# Sheet1.net
KiCad netlist of a schematic drawn in Altium Designer
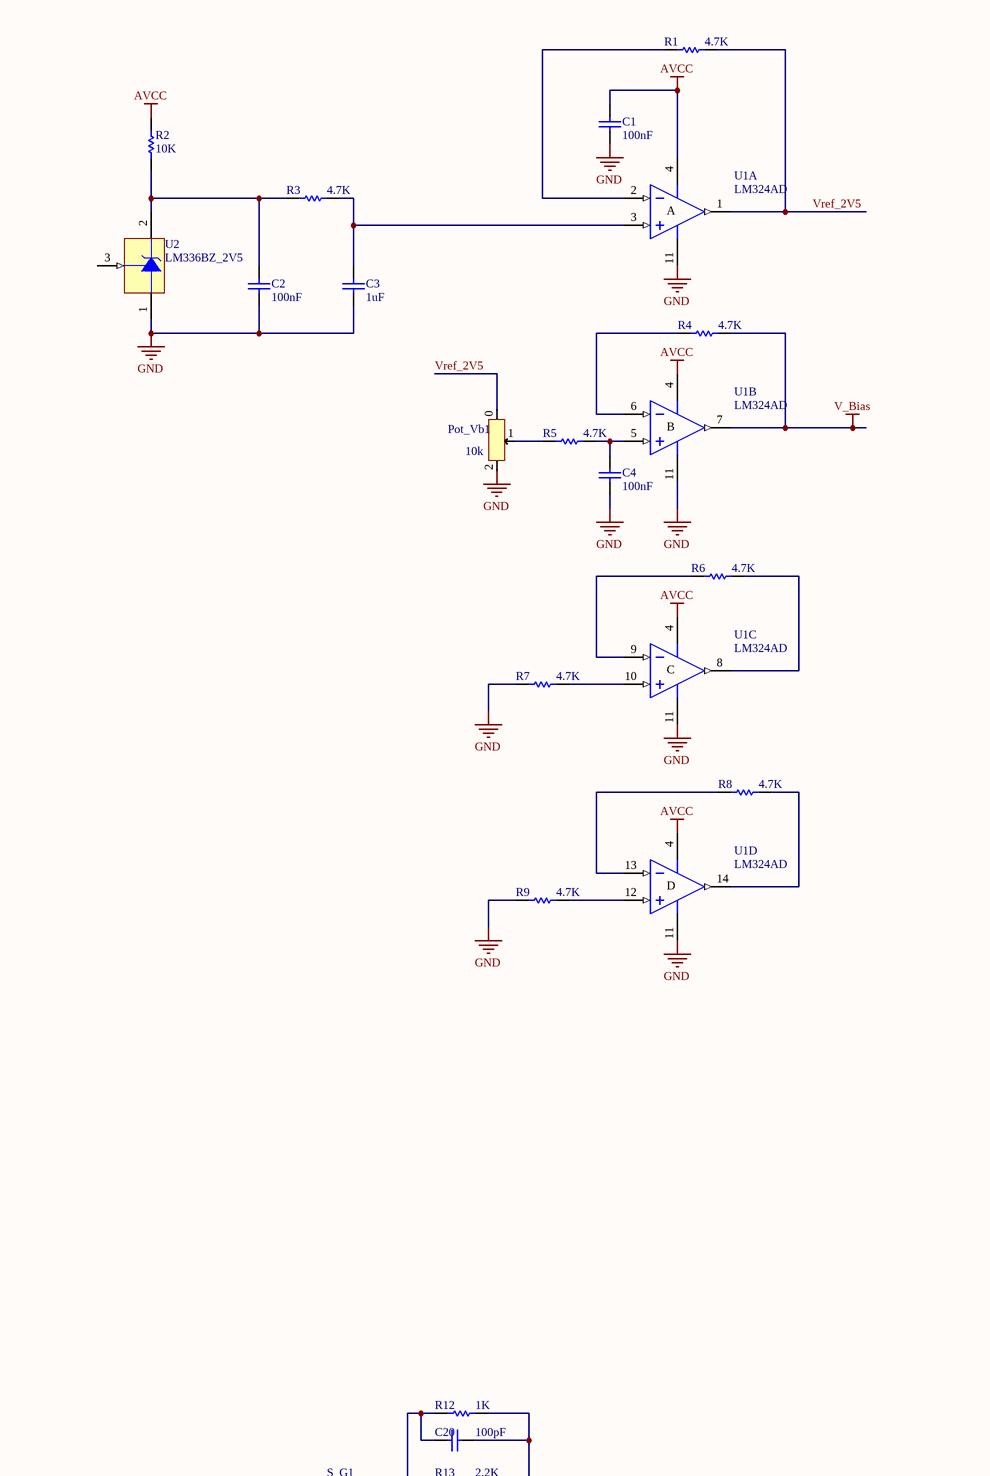
[diagram p0: Sheet1.SchDoc, top left]
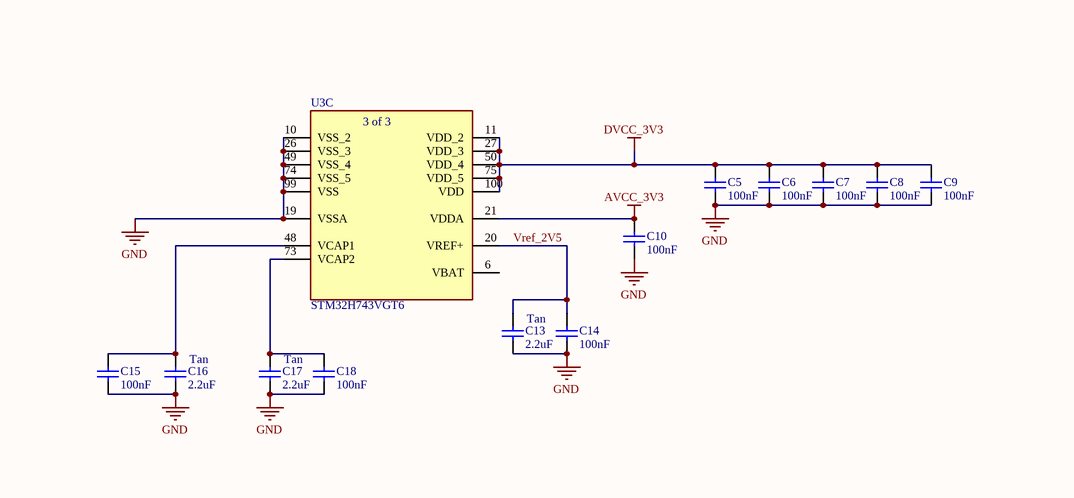
[diagram p1: Sheet1.SchDoc, top middle]
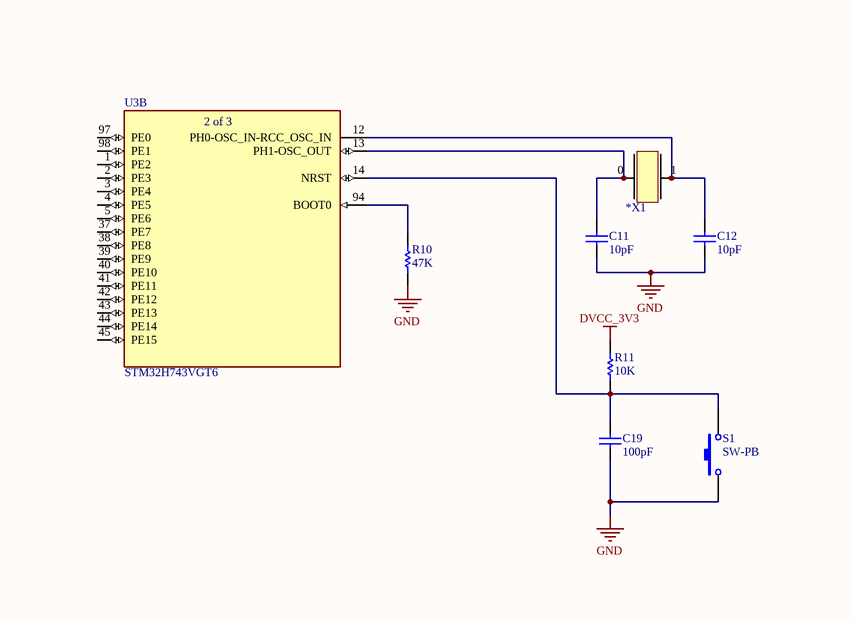
[diagram p2: Sheet1.SchDoc, top right]
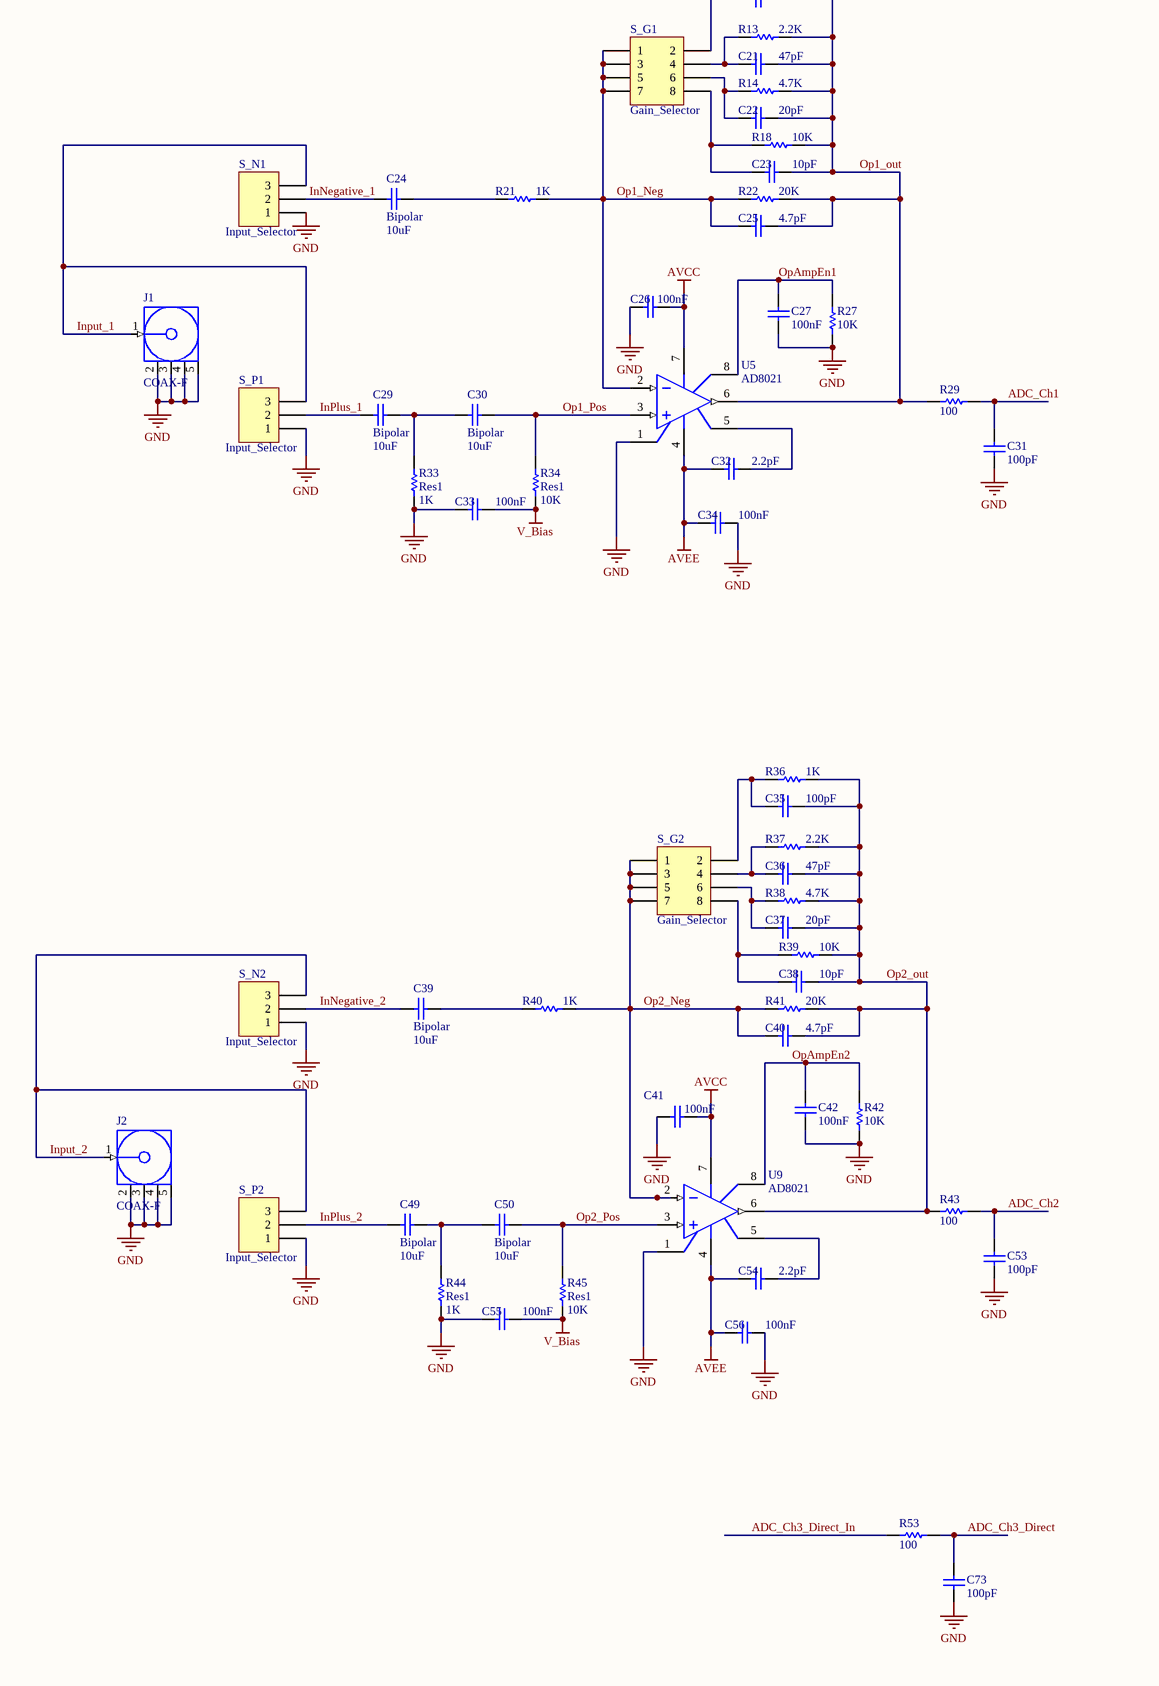
[diagram p3: Sheet1.SchDoc, bottom left]
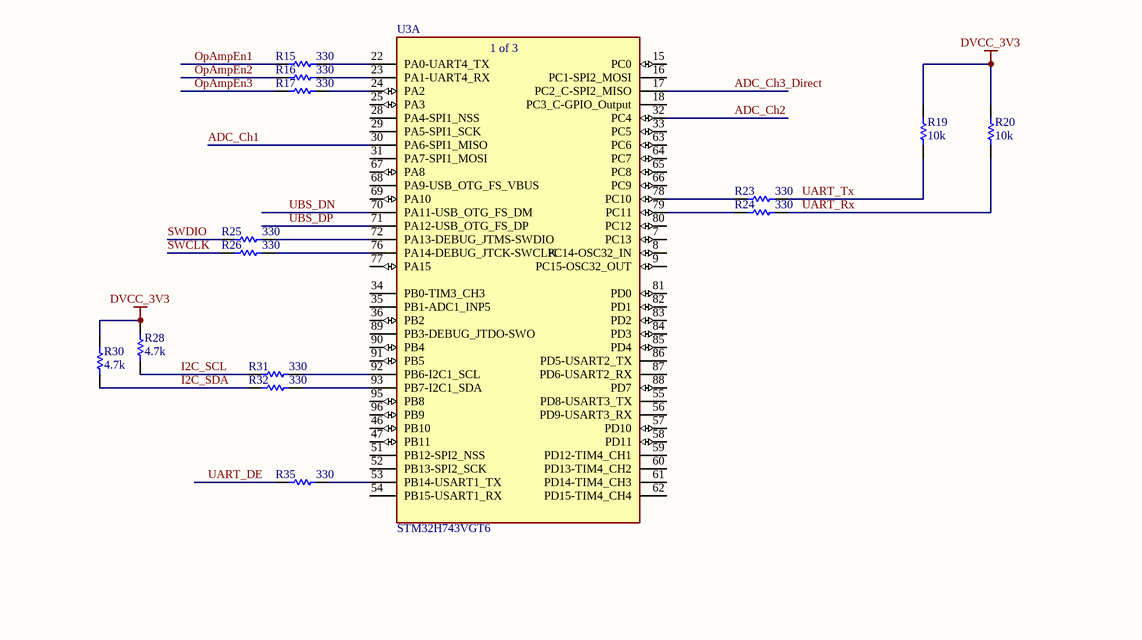
[diagram p4: Sheet1.SchDoc, bottom middle]
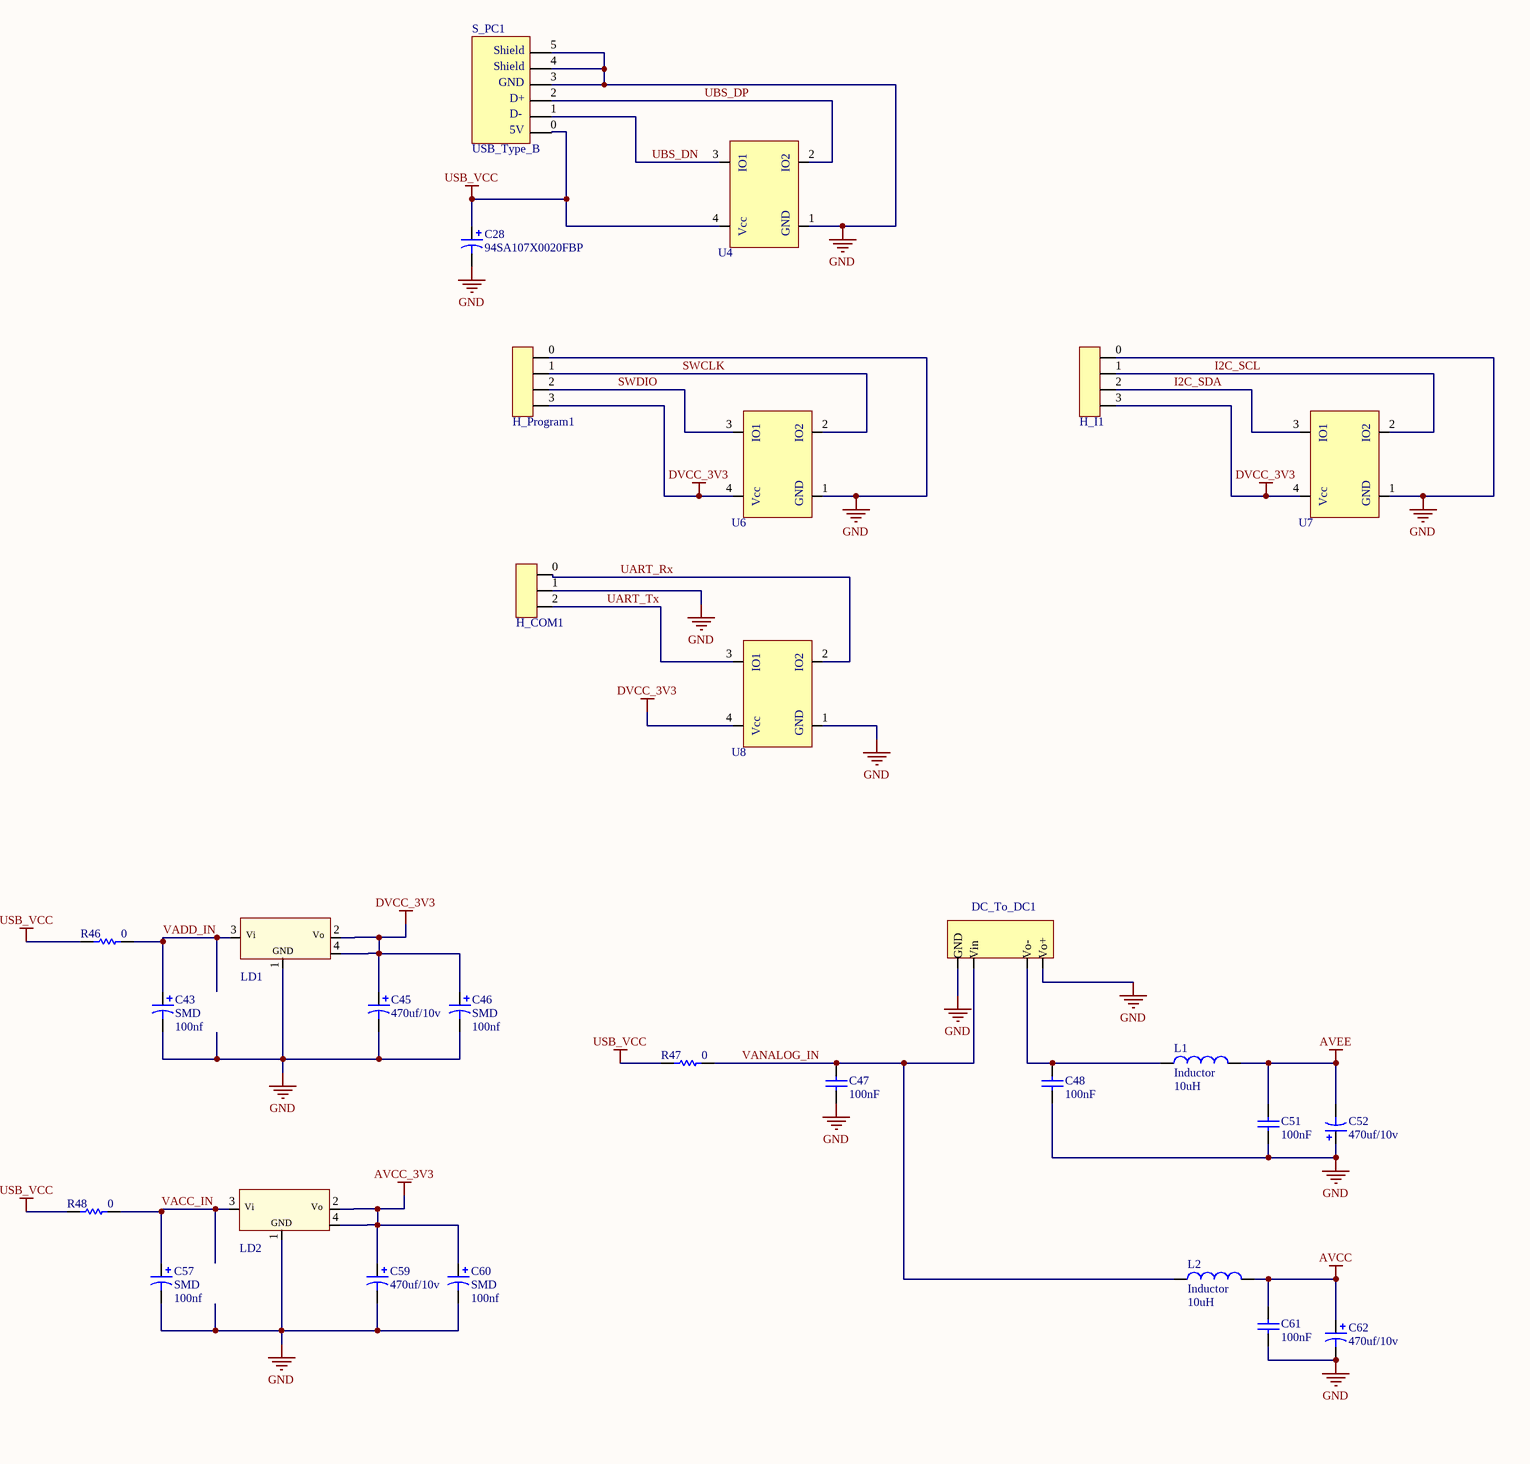
[diagram p5: Sheet1.SchDoc, bottom right]

(export (version "E")
  (design (tool "Eeschema 10.0.6"))
  (components
    (comp (ref "*X1")
      (value "XTAl_Large")
      (footprint "XTAL_Large")
      (libsource (lib "Integrated_Library") (part "XTAl_Large"))
    )
    (comp (ref "C1")
      (value "100nF")
      (footprint "C0805")
      (description "Capacitor")
      (fields (field (name "Comment") "Bipolar") (field (name "PUBLISHER") "Altium Limited"))
      (libsource (lib "Miscellaneous Devices") (part "Cap"))
    )
    (comp (ref "C2")
      (value "100nF")
      (footprint "C0805")
      (description "Capacitor")
      (fields (field (name "Comment") "Bipolar") (field (name "PUBLISHER") "Altium Limited"))
      (libsource (lib "Miscellaneous Devices") (part "Cap"))
    )
    (comp (ref "C3")
      (value "1uF")
      (footprint "C0805")
      (description "Capacitor")
      (fields (field (name "Comment") "Bipolar") (field (name "PUBLISHER") "Altium Limited"))
      (libsource (lib "Miscellaneous Devices") (part "Cap"))
    )
    (comp (ref "C4")
      (value "100nF")
      (footprint "C0805")
      (description "Capacitor")
      (fields (field (name "Comment") "Bipolar") (field (name "PUBLISHER") "Altium Limited"))
      (libsource (lib "Miscellaneous Devices") (part "Cap"))
    )
    (comp (ref "C5")
      (value "100nF")
      (footprint "C0805")
      (description "Capacitor")
      (fields (field (name "Comment") "Bipolar") (field (name "PUBLISHER") "Altium Limited"))
      (libsource (lib "Miscellaneous Devices") (part "Cap"))
    )
    (comp (ref "C6")
      (value "100nF")
      (footprint "C0805")
      (description "Capacitor")
      (fields (field (name "Comment") "Bipolar") (field (name "PUBLISHER") "Altium Limited"))
      (libsource (lib "Miscellaneous Devices") (part "Cap"))
    )
    (comp (ref "C7")
      (value "100nF")
      (footprint "C0805")
      (description "Capacitor")
      (fields (field (name "Comment") "Bipolar") (field (name "PUBLISHER") "Altium Limited"))
      (libsource (lib "Miscellaneous Devices") (part "Cap"))
    )
    (comp (ref "C8")
      (value "100nF")
      (footprint "C0805")
      (description "Capacitor")
      (fields (field (name "Comment") "Bipolar") (field (name "PUBLISHER") "Altium Limited"))
      (libsource (lib "Miscellaneous Devices") (part "Cap"))
    )
    (comp (ref "C9")
      (value "100nF")
      (footprint "C0805")
      (description "Capacitor")
      (fields (field (name "Comment") "Bipolar") (field (name "PUBLISHER") "Altium Limited"))
      (libsource (lib "Miscellaneous Devices") (part "Cap"))
    )
    (comp (ref "C10")
      (value "100nF")
      (footprint "C0805")
      (description "Capacitor")
      (fields (field (name "Comment") "Bipolar") (field (name "PUBLISHER") "Altium Limited"))
      (libsource (lib "Miscellaneous Devices") (part "Cap"))
    )
    (comp (ref "C11")
      (value "10pF")
      (footprint "C0805")
      (description "Capacitor")
      (fields (field (name "Comment") "Bipolar") (field (name "PUBLISHER") "Altium Limited"))
      (libsource (lib "Miscellaneous Devices") (part "Cap"))
    )
    (comp (ref "C12")
      (value "10pF")
      (footprint "C0805")
      (description "Capacitor")
      (fields (field (name "Comment") "Bipolar") (field (name "PUBLISHER") "Altium Limited"))
      (libsource (lib "Miscellaneous Devices") (part "Cap"))
    )
    (comp (ref "C13")
      (value "Tan")
      (footprint "C1210")
      (description "Capacitor")
      (fields (field (name "ALTIUM_VALUE") "2.2uF") (field (name "PUBLISHER") "Altium Limited"))
      (libsource (lib "Miscellaneous Devices") (part "Cap"))
    )
    (comp (ref "C14")
      (value "100nF")
      (footprint "C0805")
      (description "Capacitor")
      (fields (field (name "Comment") "Bipolar") (field (name "PUBLISHER") "Altium Limited"))
      (libsource (lib "Miscellaneous Devices") (part "Cap"))
    )
    (comp (ref "C15")
      (value "100nF")
      (footprint "C0805")
      (description "Capacitor")
      (fields (field (name "Comment") "Bipolar") (field (name "PUBLISHER") "Altium Limited"))
      (libsource (lib "Miscellaneous Devices") (part "Cap"))
    )
    (comp (ref "C16")
      (value "Tan")
      (footprint "C1210")
      (description "Capacitor")
      (fields (field (name "ALTIUM_VALUE") "2.2uF") (field (name "PUBLISHER") "Altium Limited"))
      (libsource (lib "Miscellaneous Devices") (part "Cap"))
    )
    (comp (ref "C17")
      (value "Tan")
      (footprint "C1210")
      (description "Capacitor")
      (fields (field (name "ALTIUM_VALUE") "2.2uF") (field (name "PUBLISHER") "Altium Limited"))
      (libsource (lib "Miscellaneous Devices") (part "Cap"))
    )
    (comp (ref "C18")
      (value "100nF")
      (footprint "C0805")
      (description "Capacitor")
      (fields (field (name "Comment") "Bipolar") (field (name "PUBLISHER") "Altium Limited"))
      (libsource (lib "Miscellaneous Devices") (part "Cap"))
    )
    (comp (ref "C19")
      (value "100pF")
      (footprint "C0805")
      (description "Capacitor")
      (fields (field (name "Comment") "Bipolar") (field (name "PUBLISHER") "Altium Limited"))
      (libsource (lib "Miscellaneous Devices") (part "Cap"))
    )
    (comp (ref "C20")
      (value "100pF")
      (footprint "C0805")
      (description "Capacitor")
      (fields (field (name "Comment") "Bipolar") (field (name "PUBLISHER") "Altium Limited"))
      (libsource (lib "Miscellaneous Devices") (part "Cap"))
    )
    (comp (ref "C21")
      (value "47pF")
      (footprint "C0805")
      (description "Capacitor")
      (fields (field (name "Comment") "Bipolar") (field (name "PUBLISHER") "Altium Limited"))
      (libsource (lib "Miscellaneous Devices") (part "Cap"))
    )
    (comp (ref "C22")
      (value "20pF")
      (footprint "C0805")
      (description "Capacitor")
      (fields (field (name "Comment") "Bipolar") (field (name "PUBLISHER") "Altium Limited"))
      (libsource (lib "Miscellaneous Devices") (part "Cap"))
    )
    (comp (ref "C23")
      (value "10pF")
      (footprint "C0805")
      (description "Capacitor")
      (fields (field (name "Comment") "Bipolar") (field (name "PUBLISHER") "Altium Limited"))
      (libsource (lib "Miscellaneous Devices") (part "Cap"))
    )
    (comp (ref "C24")
      (value "Bipolar")
      (footprint "HA-N3")
      (description "Capacitor")
      (fields (field (name "ALTIUM_VALUE") "10uF") (field (name "PUBLISHER") "Altium Limited"))
      (libsource (lib "Miscellaneous Devices") (part "Cap"))
    )
    (comp (ref "C25")
      (value "4.7pF")
      (footprint "C0805")
      (description "Capacitor")
      (fields (field (name "Comment") "Bipolar") (field (name "PUBLISHER") "Altium Limited"))
      (libsource (lib "Miscellaneous Devices") (part "Cap"))
    )
    (comp (ref "C26")
      (value "100nF")
      (footprint "C0805")
      (description "Capacitor")
      (fields (field (name "Comment") "Bipolar") (field (name "PUBLISHER") "Altium Limited"))
      (libsource (lib "Miscellaneous Devices") (part "Cap"))
    )
    (comp (ref "C27")
      (value "100nF")
      (footprint "C0805")
      (description "Capacitor")
      (fields (field (name "Comment") "Bipolar") (field (name "PUBLISHER") "Altium Limited"))
      (libsource (lib "Miscellaneous Devices") (part "Cap"))
    )
    (comp (ref "C28")
      (value "94SA107X0020FBP")
      (footprint "F")
      (description "Solid Aluminum Capacitor with Organic Semiconductor Electrolyte: 100uF, 20V, Bulk Pack")
      (fields (field (name "PUBLISHER") "Altium Limited"))
      (libsource (lib "Vishay Electrolytic Radial-Lead Capacitor") (part "94SA107X0020FBP"))
    )
    (comp (ref "C29")
      (value "Bipolar")
      (footprint "HA-N3")
      (description "Capacitor")
      (fields (field (name "ALTIUM_VALUE") "10uF") (field (name "PUBLISHER") "Altium Limited"))
      (libsource (lib "Miscellaneous Devices") (part "Cap"))
    )
    (comp (ref "C30")
      (value "Bipolar")
      (footprint "HA-N3")
      (description "Capacitor")
      (fields (field (name "ALTIUM_VALUE") "10uF") (field (name "PUBLISHER") "Altium Limited"))
      (libsource (lib "Miscellaneous Devices") (part "Cap"))
    )
    (comp (ref "C31")
      (value "100pF")
      (footprint "C0805")
      (description "Capacitor")
      (fields (field (name "Comment") "Bipolar") (field (name "PUBLISHER") "Altium Limited"))
      (libsource (lib "Miscellaneous Devices") (part "Cap"))
    )
    (comp (ref "C32")
      (value "2.2pF")
      (footprint "C0805")
      (description "Capacitor")
      (fields (field (name "Comment") "Bipolar") (field (name "PUBLISHER") "Altium Limited"))
      (libsource (lib "Miscellaneous Devices") (part "Cap"))
    )
    (comp (ref "C33")
      (value "100nF")
      (footprint "C0805")
      (description "Capacitor")
      (fields (field (name "Comment") "Bipolar") (field (name "PUBLISHER") "Altium Limited"))
      (libsource (lib "Miscellaneous Devices") (part "Cap"))
    )
    (comp (ref "C34")
      (value "100nF")
      (footprint "C0805")
      (description "Capacitor")
      (fields (field (name "Comment") "Bipolar") (field (name "PUBLISHER") "Altium Limited"))
      (libsource (lib "Miscellaneous Devices") (part "Cap"))
    )
    (comp (ref "C35")
      (value "100pF")
      (footprint "C0805")
      (description "Capacitor")
      (fields (field (name "Comment") "Bipolar") (field (name "PUBLISHER") "Altium Limited"))
      (libsource (lib "Miscellaneous Devices") (part "Cap"))
    )
    (comp (ref "C36")
      (value "47pF")
      (footprint "C0805")
      (description "Capacitor")
      (fields (field (name "Comment") "Bipolar") (field (name "PUBLISHER") "Altium Limited"))
      (libsource (lib "Miscellaneous Devices") (part "Cap"))
    )
    (comp (ref "C37")
      (value "20pF")
      (footprint "C0805")
      (description "Capacitor")
      (fields (field (name "Comment") "Bipolar") (field (name "PUBLISHER") "Altium Limited"))
      (libsource (lib "Miscellaneous Devices") (part "Cap"))
    )
    (comp (ref "C38")
      (value "10pF")
      (footprint "C0805")
      (description "Capacitor")
      (fields (field (name "Comment") "Bipolar") (field (name "PUBLISHER") "Altium Limited"))
      (libsource (lib "Miscellaneous Devices") (part "Cap"))
    )
    (comp (ref "C39")
      (value "Bipolar")
      (footprint "HA-N3")
      (description "Capacitor")
      (fields (field (name "ALTIUM_VALUE") "10uF") (field (name "PUBLISHER") "Altium Limited"))
      (libsource (lib "Miscellaneous Devices") (part "Cap"))
    )
    (comp (ref "C40")
      (value "4.7pF")
      (footprint "C0805")
      (description "Capacitor")
      (fields (field (name "Comment") "Bipolar") (field (name "PUBLISHER") "Altium Limited"))
      (libsource (lib "Miscellaneous Devices") (part "Cap"))
    )
    (comp (ref "C41")
      (value "100nF")
      (footprint "C0805")
      (description "Capacitor")
      (fields (field (name "Comment") "Bipolar") (field (name "PUBLISHER") "Altium Limited"))
      (libsource (lib "Miscellaneous Devices") (part "Cap"))
    )
    (comp (ref "C42")
      (value "100nF")
      (footprint "C0805")
      (description "Capacitor")
      (fields (field (name "Comment") "Bipolar") (field (name "PUBLISHER") "Altium Limited"))
      (libsource (lib "Miscellaneous Devices") (part "Cap"))
    )
    (comp (ref "C43")
      (value "SMD")
      (footprint "C0805")
      (description "Polarized Capacitor (Surface Mount)")
      (fields (field (name "ALTIUM_VALUE") "100nf") (field (name "PUBLISHER") "Altium Limited"))
      (libsource (lib "Miscellaneous Devices") (part "Cap Pol3"))
    )
    (comp (ref "C45")
      (value "470uf/10v")
      (footprint "CAPPR3.5-8X11.5")
      (description "Aluminum Electrolytic Capacitor, Radial Style with Long Leads: 470uF, 16V")
      (fields (field (name "PUBLISHER") "Altium Limited"))
      (libsource (lib "Vishay Roederstein Electrolytic Radial-Lead Capacitor") (part "EKA00DC347D00"))
    )
    (comp (ref "C46")
      (value "SMD")
      (footprint "C0805")
      (description "Polarized Capacitor (Surface Mount)")
      (fields (field (name "ALTIUM_VALUE") "100nf") (field (name "PUBLISHER") "Altium Limited"))
      (libsource (lib "Miscellaneous Devices") (part "Cap Pol3"))
    )
    (comp (ref "C47")
      (value "100nF")
      (footprint "C0805")
      (description "Capacitor")
      (fields (field (name "Comment") "Bipolar") (field (name "PUBLISHER") "Altium Limited"))
      (libsource (lib "Miscellaneous Devices") (part "Cap"))
    )
    (comp (ref "C48")
      (value "100nF")
      (footprint "C0805")
      (description "Capacitor")
      (fields (field (name "Comment") "Bipolar") (field (name "PUBLISHER") "Altium Limited"))
      (libsource (lib "Miscellaneous Devices") (part "Cap"))
    )
    (comp (ref "C49")
      (value "Bipolar")
      (footprint "HA-N3")
      (description "Capacitor")
      (fields (field (name "ALTIUM_VALUE") "10uF") (field (name "PUBLISHER") "Altium Limited"))
      (libsource (lib "Miscellaneous Devices") (part "Cap"))
    )
    (comp (ref "C50")
      (value "Bipolar")
      (footprint "HA-N3")
      (description "Capacitor")
      (fields (field (name "ALTIUM_VALUE") "10uF") (field (name "PUBLISHER") "Altium Limited"))
      (libsource (lib "Miscellaneous Devices") (part "Cap"))
    )
    (comp (ref "C51")
      (value "100nF")
      (footprint "C0805")
      (description "Capacitor")
      (fields (field (name "Comment") "Bipolar") (field (name "PUBLISHER") "Altium Limited"))
      (libsource (lib "Miscellaneous Devices") (part "Cap"))
    )
    (comp (ref "C52")
      (value "470uf/10v")
      (footprint "CAPPR3.5-8X11.5")
      (description "Aluminum Electrolytic Capacitor, Radial Style with Long Leads: 470uF, 16V")
      (fields (field (name "PUBLISHER") "Altium Limited"))
      (libsource (lib "Vishay Roederstein Electrolytic Radial-Lead Capacitor") (part "EKA00DC347D00"))
    )
    (comp (ref "C53")
      (value "100pF")
      (footprint "C0805")
      (description "Capacitor")
      (fields (field (name "Comment") "Bipolar") (field (name "PUBLISHER") "Altium Limited"))
      (libsource (lib "Miscellaneous Devices") (part "Cap"))
    )
    (comp (ref "C54")
      (value "2.2pF")
      (footprint "C0805")
      (description "Capacitor")
      (fields (field (name "Comment") "Bipolar") (field (name "PUBLISHER") "Altium Limited"))
      (libsource (lib "Miscellaneous Devices") (part "Cap"))
    )
    (comp (ref "C55")
      (value "100nF")
      (footprint "C0805")
      (description "Capacitor")
      (fields (field (name "Comment") "Bipolar") (field (name "PUBLISHER") "Altium Limited"))
      (libsource (lib "Miscellaneous Devices") (part "Cap"))
    )
    (comp (ref "C56")
      (value "100nF")
      (footprint "C0805")
      (description "Capacitor")
      (fields (field (name "Comment") "Bipolar") (field (name "PUBLISHER") "Altium Limited"))
      (libsource (lib "Miscellaneous Devices") (part "Cap"))
    )
    (comp (ref "C57")
      (value "SMD")
      (footprint "C0805")
      (description "Polarized Capacitor (Surface Mount)")
      (fields (field (name "ALTIUM_VALUE") "100nf") (field (name "PUBLISHER") "Altium Limited"))
      (libsource (lib "Miscellaneous Devices") (part "Cap Pol3"))
    )
    (comp (ref "C59")
      (value "470uf/10v")
      (footprint "CAPPR3.5-8X11.5")
      (description "Aluminum Electrolytic Capacitor, Radial Style with Long Leads: 470uF, 16V")
      (fields (field (name "PUBLISHER") "Altium Limited"))
      (libsource (lib "Vishay Roederstein Electrolytic Radial-Lead Capacitor") (part "EKA00DC347D00"))
    )
    (comp (ref "C60")
      (value "SMD")
      (footprint "C0805")
      (description "Polarized Capacitor (Surface Mount)")
      (fields (field (name "ALTIUM_VALUE") "100nf") (field (name "PUBLISHER") "Altium Limited"))
      (libsource (lib "Miscellaneous Devices") (part "Cap Pol3"))
    )
    (comp (ref "C61")
      (value "100nF")
      (footprint "C0805")
      (description "Capacitor")
      (fields (field (name "Comment") "Bipolar") (field (name "PUBLISHER") "Altium Limited"))
      (libsource (lib "Miscellaneous Devices") (part "Cap"))
    )
    (comp (ref "C62")
      (value "470uf/10v")
      (footprint "CAPPR3.5-8X11.5")
      (description "Aluminum Electrolytic Capacitor, Radial Style with Long Leads: 470uF, 16V")
      (fields (field (name "PUBLISHER") "Altium Limited"))
      (libsource (lib "Vishay Roederstein Electrolytic Radial-Lead Capacitor") (part "EKA00DC347D00"))
    )
    (comp (ref "C73")
      (value "100pF")
      (footprint "C0805")
      (description "Capacitor")
      (fields (field (name "Comment") "Bipolar") (field (name "PUBLISHER") "Altium Limited"))
      (libsource (lib "Miscellaneous Devices") (part "Cap"))
    )
    (comp (ref "DC_To_DC1")
      (value "DC_To_DC")
      (footprint "DC_To_DC")
      (libsource (lib "Integrated_Library") (part "DC_To_DC"))
    )
    (comp (ref "H_COM1")
      (value "Header_3Pin")
      (footprint "Header_3Pin")
      (libsource (lib "Integrated_Library") (part "Header_3Pin"))
    )
    (comp (ref "H_I1")
      (value "Header_4Pin")
      (footprint "Header_4Pin")
      (libsource (lib "Integrated_Library") (part "Header_4Pin"))
    )
    (comp (ref "H_Program1")
      (value "Header_4Pin")
      (footprint "Header_4Pin")
      (libsource (lib "Integrated_Library") (part "Header_4Pin"))
    )
    (comp (ref "J1")
      (value "COAX-F")
      (footprint "MCX5.08-H5")
      (fields (field (name "PUBLISHER") "Altium Limited"))
      (libsource (lib "Miscellaneous Connectors") (part "COAX-F"))
    )
    (comp (ref "J2")
      (value "COAX-F")
      (footprint "MCX5.08-H5")
      (fields (field (name "PUBLISHER") "Altium Limited"))
      (libsource (lib "Miscellaneous Connectors") (part "COAX-F"))
    )
    (comp (ref "L1")
      (value "Inductor")
      (footprint "6-0805_M")
      (fields (field (name "ALTIUM_VALUE") "10uH") (field (name "PUBLISHER") "Altium Limited"))
      (libsource (lib "Miscellaneous Devices") (part "Inductor"))
    )
    (comp (ref "L2")
      (value "Inductor")
      (footprint "6-0805_M")
      (fields (field (name "ALTIUM_VALUE") "10uH") (field (name "PUBLISHER") "Altium Limited"))
      (libsource (lib "Miscellaneous Devices") (part "Inductor"))
    )
    (comp (ref "LD1")
      (value "LD33")
      (footprint "SOT230P")
      (libsource (lib "Integrated_Library") (part "LD33"))
    )
    (comp (ref "LD2")
      (value "LD33")
      (footprint "SOT230P")
      (libsource (lib "Integrated_Library") (part "LD33"))
    )
    (comp (ref "Pot_Vb1")
      (value "10k")
      (footprint "MultiTurn")
      (libsource (lib "Integrated_Library") (part "Pot"))
    )
    (comp (ref "R1")
      (value "4.7K")
      (footprint "6-0805_L")
      (description "Resistor")
      (fields (field (name "Comment") "Res1") (field (name "PUBLISHER") "Altium Limited"))
      (libsource (lib "Miscellaneous Devices") (part "Res1"))
    )
    (comp (ref "R2")
      (value "10K")
      (footprint "6-0805_L")
      (description "Resistor")
      (fields (field (name "Comment") "Res1") (field (name "PUBLISHER") "Altium Limited"))
      (libsource (lib "Miscellaneous Devices") (part "Res1"))
    )
    (comp (ref "R3")
      (value "4.7K")
      (footprint "6-0805_L")
      (description "Resistor")
      (fields (field (name "Comment") "Res1") (field (name "PUBLISHER") "Altium Limited"))
      (libsource (lib "Miscellaneous Devices") (part "Res1"))
    )
    (comp (ref "R4")
      (value "4.7K")
      (footprint "6-0805_L")
      (description "Resistor")
      (fields (field (name "Comment") "Res1") (field (name "PUBLISHER") "Altium Limited"))
      (libsource (lib "Miscellaneous Devices") (part "Res1"))
    )
    (comp (ref "R5")
      (value "4.7K")
      (footprint "6-0805_L")
      (description "Resistor")
      (fields (field (name "Comment") "Res1") (field (name "PUBLISHER") "Altium Limited"))
      (libsource (lib "Miscellaneous Devices") (part "Res1"))
    )
    (comp (ref "R6")
      (value "4.7K")
      (footprint "6-0805_L")
      (description "Resistor")
      (fields (field (name "Comment") "Res1") (field (name "PUBLISHER") "Altium Limited"))
      (libsource (lib "Miscellaneous Devices") (part "Res1"))
    )
    (comp (ref "R7")
      (value "4.7K")
      (footprint "6-0805_L")
      (description "Resistor")
      (fields (field (name "Comment") "Res1") (field (name "PUBLISHER") "Altium Limited"))
      (libsource (lib "Miscellaneous Devices") (part "Res1"))
    )
    (comp (ref "R8")
      (value "4.7K")
      (footprint "6-0805_L")
      (description "Resistor")
      (fields (field (name "Comment") "Res1") (field (name "PUBLISHER") "Altium Limited"))
      (libsource (lib "Miscellaneous Devices") (part "Res1"))
    )
    (comp (ref "R9")
      (value "4.7K")
      (footprint "6-0805_L")
      (description "Resistor")
      (fields (field (name "Comment") "Res1") (field (name "PUBLISHER") "Altium Limited"))
      (libsource (lib "Miscellaneous Devices") (part "Res1"))
    )
    (comp (ref "R10")
      (value "47K")
      (footprint "6-0805_L")
      (description "Resistor")
      (fields (field (name "Comment") "Res1") (field (name "PUBLISHER") "Altium Limited"))
      (libsource (lib "Miscellaneous Devices") (part "Res1"))
    )
    (comp (ref "R11")
      (value "10K")
      (footprint "6-0805_L")
      (description "Resistor")
      (fields (field (name "Comment") "Res1") (field (name "PUBLISHER") "Altium Limited"))
      (libsource (lib "Miscellaneous Devices") (part "Res1"))
    )
    (comp (ref "R12")
      (value "1K")
      (footprint "6-0805_L")
      (description "Resistor")
      (fields (field (name "Comment") "Res1") (field (name "PUBLISHER") "Altium Limited"))
      (libsource (lib "Miscellaneous Devices") (part "Res1"))
    )
    (comp (ref "R13")
      (value "2.2K")
      (footprint "6-0805_L")
      (description "Resistor")
      (fields (field (name "Comment") "Res1") (field (name "PUBLISHER") "Altium Limited"))
      (libsource (lib "Miscellaneous Devices") (part "Res1"))
    )
    (comp (ref "R14")
      (value "4.7K")
      (footprint "6-0805_L")
      (description "Resistor")
      (fields (field (name "Comment") "Res1") (field (name "PUBLISHER") "Altium Limited"))
      (libsource (lib "Miscellaneous Devices") (part "Res1"))
    )
    (comp (ref "R15")
      (value "330")
      (footprint "6-0805_L")
      (description "Resistor")
      (fields (field (name "Comment") "Res1") (field (name "PUBLISHER") "Altium Limited"))
      (libsource (lib "Miscellaneous Devices") (part "Res1"))
    )
    (comp (ref "R16")
      (value "330")
      (footprint "6-0805_L")
      (description "Resistor")
      (fields (field (name "Comment") "Res1") (field (name "PUBLISHER") "Altium Limited"))
      (libsource (lib "Miscellaneous Devices") (part "Res1"))
    )
    (comp (ref "R17")
      (value "330")
      (footprint "6-0805_L")
      (description "Resistor")
      (fields (field (name "Comment") "Res1") (field (name "PUBLISHER") "Altium Limited"))
      (libsource (lib "Miscellaneous Devices") (part "Res1"))
    )
    (comp (ref "R18")
      (value "10K")
      (footprint "6-0805_L")
      (description "Resistor")
      (fields (field (name "Comment") "Res1") (field (name "PUBLISHER") "Altium Limited"))
      (libsource (lib "Miscellaneous Devices") (part "Res1"))
    )
    (comp (ref "R19")
      (value "10k")
      (footprint "6-0805_L")
      (description "Resistor")
      (fields (field (name "Comment") "Res1") (field (name "PUBLISHER") "Altium Limited"))
      (libsource (lib "Miscellaneous Devices") (part "Res1"))
    )
    (comp (ref "R20")
      (value "10k")
      (footprint "6-0805_L")
      (description "Resistor")
      (fields (field (name "Comment") "Res1") (field (name "PUBLISHER") "Altium Limited"))
      (libsource (lib "Miscellaneous Devices") (part "Res1"))
    )
    (comp (ref "R21")
      (value "1K")
      (footprint "6-0805_L")
      (description "Resistor")
      (fields (field (name "Comment") "Res1") (field (name "PUBLISHER") "Altium Limited"))
      (libsource (lib "Miscellaneous Devices") (part "Res1"))
    )
    (comp (ref "R22")
      (value "20K")
      (footprint "6-0805_L")
      (description "Resistor")
      (fields (field (name "Comment") "Res1") (field (name "PUBLISHER") "Altium Limited"))
      (libsource (lib "Miscellaneous Devices") (part "Res1"))
    )
    (comp (ref "R23")
      (value "330")
      (footprint "6-0805_L")
      (description "Resistor")
      (fields (field (name "Comment") "Res1") (field (name "PUBLISHER") "Altium Limited"))
      (libsource (lib "Miscellaneous Devices") (part "Res1"))
    )
    (comp (ref "R24")
      (value "330")
      (footprint "6-0805_L")
      (description "Resistor")
      (fields (field (name "Comment") "Res1") (field (name "PUBLISHER") "Altium Limited"))
      (libsource (lib "Miscellaneous Devices") (part "Res1"))
    )
    (comp (ref "R25")
      (value "330")
      (footprint "6-0805_L")
      (description "Resistor")
      (fields (field (name "Comment") "Res1") (field (name "PUBLISHER") "Altium Limited"))
      (libsource (lib "Miscellaneous Devices") (part "Res1"))
    )
    (comp (ref "R26")
      (value "330")
      (footprint "6-0805_L")
      (description "Resistor")
      (fields (field (name "Comment") "Res1") (field (name "PUBLISHER") "Altium Limited"))
      (libsource (lib "Miscellaneous Devices") (part "Res1"))
    )
    (comp (ref "R27")
      (value "10K")
      (footprint "6-0805_L")
      (description "Resistor")
      (fields (field (name "Comment") "Res1") (field (name "PUBLISHER") "Altium Limited"))
      (libsource (lib "Miscellaneous Devices") (part "Res1"))
    )
    (comp (ref "R28")
      (value "4.7k")
      (footprint "6-0805_L")
      (description "Resistor")
      (fields (field (name "Comment") "Res1") (field (name "PUBLISHER") "Altium Limited"))
      (libsource (lib "Miscellaneous Devices") (part "Res1"))
    )
    (comp (ref "R29")
      (value "100")
      (footprint "6-0805_L")
      (description "Resistor")
      (fields (field (name "Comment") "Res1") (field (name "PUBLISHER") "Altium Limited"))
      (libsource (lib "Miscellaneous Devices") (part "Res1"))
    )
    (comp (ref "R30")
      (value "4.7k")
      (footprint "6-0805_L")
      (description "Resistor")
      (fields (field (name "Comment") "Res1") (field (name "PUBLISHER") "Altium Limited"))
      (libsource (lib "Miscellaneous Devices") (part "Res1"))
    )
    (comp (ref "R31")
      (value "330")
      (footprint "6-0805_L")
      (description "Resistor")
      (fields (field (name "Comment") "Res1") (field (name "PUBLISHER") "Altium Limited"))
      (libsource (lib "Miscellaneous Devices") (part "Res1"))
    )
    (comp (ref "R32")
      (value "330")
      (footprint "6-0805_L")
      (description "Resistor")
      (fields (field (name "Comment") "Res1") (field (name "PUBLISHER") "Altium Limited"))
      (libsource (lib "Miscellaneous Devices") (part "Res1"))
    )
    (comp (ref "R33")
      (value "Res1")
      (footprint "6-0805_L")
      (description "Resistor")
      (fields (field (name "ALTIUM_VALUE") "1K") (field (name "PUBLISHER") "Altium Limited"))
      (libsource (lib "Miscellaneous Devices") (part "Res1"))
    )
    (comp (ref "R34")
      (value "Res1")
      (footprint "6-0805_L")
      (description "Resistor")
      (fields (field (name "ALTIUM_VALUE") "10K") (field (name "PUBLISHER") "Altium Limited"))
      (libsource (lib "Miscellaneous Devices") (part "Res1"))
    )
    (comp (ref "R35")
      (value "330")
      (footprint "6-0805_L")
      (description "Resistor")
      (fields (field (name "Comment") "Res1") (field (name "PUBLISHER") "Altium Limited"))
      (libsource (lib "Miscellaneous Devices") (part "Res1"))
    )
    (comp (ref "R36")
      (value "1K")
      (footprint "6-0805_L")
      (description "Resistor")
      (fields (field (name "Comment") "Res1") (field (name "PUBLISHER") "Altium Limited"))
      (libsource (lib "Miscellaneous Devices") (part "Res1"))
    )
    (comp (ref "R37")
      (value "2.2K")
      (footprint "6-0805_L")
      (description "Resistor")
      (fields (field (name "Comment") "Res1") (field (name "PUBLISHER") "Altium Limited"))
      (libsource (lib "Miscellaneous Devices") (part "Res1"))
    )
    (comp (ref "R38")
      (value "4.7K")
      (footprint "6-0805_L")
      (description "Resistor")
      (fields (field (name "Comment") "Res1") (field (name "PUBLISHER") "Altium Limited"))
      (libsource (lib "Miscellaneous Devices") (part "Res1"))
    )
    (comp (ref "R39")
      (value "10K")
      (footprint "6-0805_L")
      (description "Resistor")
      (fields (field (name "Comment") "Res1") (field (name "PUBLISHER") "Altium Limited"))
      (libsource (lib "Miscellaneous Devices") (part "Res1"))
    )
    (comp (ref "R40")
      (value "1K")
      (footprint "6-0805_L")
      (description "Resistor")
      (fields (field (name "Comment") "Res1") (field (name "PUBLISHER") "Altium Limited"))
      (libsource (lib "Miscellaneous Devices") (part "Res1"))
    )
    (comp (ref "R41")
      (value "20K")
      (footprint "6-0805_L")
      (description "Resistor")
      (fields (field (name "Comment") "Res1") (field (name "PUBLISHER") "Altium Limited"))
      (libsource (lib "Miscellaneous Devices") (part "Res1"))
    )
    (comp (ref "R42")
      (value "10K")
      (footprint "6-0805_L")
      (description "Resistor")
      (fields (field (name "Comment") "Res1") (field (name "PUBLISHER") "Altium Limited"))
      (libsource (lib "Miscellaneous Devices") (part "Res1"))
    )
    (comp (ref "R43")
      (value "100")
      (footprint "6-0805_L")
      (description "Resistor")
      (fields (field (name "Comment") "Res1") (field (name "PUBLISHER") "Altium Limited"))
      (libsource (lib "Miscellaneous Devices") (part "Res1"))
    )
    (comp (ref "R44")
      (value "Res1")
      (footprint "6-0805_L")
      (description "Resistor")
      (fields (field (name "ALTIUM_VALUE") "1K") (field (name "PUBLISHER") "Altium Limited"))
      (libsource (lib "Miscellaneous Devices") (part "Res1"))
    )
    (comp (ref "R45")
      (value "Res1")
      (footprint "6-0805_L")
      (description "Resistor")
      (fields (field (name "ALTIUM_VALUE") "10K") (field (name "PUBLISHER") "Altium Limited"))
      (libsource (lib "Miscellaneous Devices") (part "Res1"))
    )
    (comp (ref "R46")
      (value "0")
      (footprint "6-0805_L")
      (description "Resistor")
      (fields (field (name "Comment") "Res1") (field (name "PUBLISHER") "Altium Limited"))
      (libsource (lib "Miscellaneous Devices") (part "Res1"))
    )
    (comp (ref "R47")
      (value "0")
      (footprint "6-0805_L")
      (description "Resistor")
      (fields (field (name "Comment") "Res1") (field (name "PUBLISHER") "Altium Limited"))
      (libsource (lib "Miscellaneous Devices") (part "Res1"))
    )
    (comp (ref "R48")
      (value "0")
      (footprint "6-0805_L")
      (description "Resistor")
      (fields (field (name "Comment") "Res1") (field (name "PUBLISHER") "Altium Limited"))
      (libsource (lib "Miscellaneous Devices") (part "Res1"))
    )
    (comp (ref "R53")
      (value "100")
      (footprint "6-0805_L")
      (description "Resistor")
      (fields (field (name "Comment") "Res1") (field (name "PUBLISHER") "Altium Limited"))
      (libsource (lib "Miscellaneous Devices") (part "Res1"))
    )
    (comp (ref "S1")
      (value "SW-PB")
      (footprint "SPST-2")
      (description "Switch")
      (fields (field (name "PUBLISHER") "Altium Limited"))
      (libsource (lib "Miscellaneous Devices") (part "SW-PB"))
    )
    (comp (ref "S_G1")
      (value "Gain_Selector")
      (footprint "HDR2X4")
      (description "Header, 4-Pin, Dual row")
      (fields (field (name "PUBLISHER") "Altium Limited"))
      (libsource (lib "Miscellaneous Connectors") (part "Header 4X2"))
    )
    (comp (ref "S_G2")
      (value "Gain_Selector")
      (footprint "HDR2X4")
      (description "Header, 4-Pin, Dual row")
      (fields (field (name "PUBLISHER") "Altium Limited"))
      (libsource (lib "Miscellaneous Connectors") (part "Header 4X2"))
    )
    (comp (ref "S_N1")
      (value "Input_Selector")
      (footprint "HDR1X3")
      (description "Header, 3-Pin")
      (fields (field (name "PUBLISHER") "Altium Limited"))
      (libsource (lib "Miscellaneous Connectors") (part "Header 3"))
    )
    (comp (ref "S_N2")
      (value "Input_Selector")
      (footprint "HDR1X3")
      (description "Header, 3-Pin")
      (fields (field (name "PUBLISHER") "Altium Limited"))
      (libsource (lib "Miscellaneous Connectors") (part "Header 3"))
    )
    (comp (ref "S_P1")
      (value "Input_Selector")
      (footprint "HDR1X3")
      (description "Header, 3-Pin")
      (fields (field (name "PUBLISHER") "Altium Limited"))
      (libsource (lib "Miscellaneous Connectors") (part "Header 3"))
    )
    (comp (ref "S_P2")
      (value "Input_Selector")
      (footprint "HDR1X3")
      (description "Header, 3-Pin")
      (fields (field (name "PUBLISHER") "Altium Limited"))
      (libsource (lib "Miscellaneous Connectors") (part "Header 3"))
    )
    (comp (ref "S_PC1")
      (value "USB_Type_B")
      (footprint "USB_Type_B")
      (libsource (lib "Integrated_Library") (part "USB_Type_B"))
    )
    (comp (ref "U1")
      (value "LM324AD")
      (footprint "SO14_N")
      (description "Low-Power Quad Operational Amplifier")
      (fields (field (name "PUBLISHER") "Altium Limited"))
      (libsource (lib "ST Operational Amplifier") (part "LM324AD"))
    )
    (comp (ref "U2")
      (value "LM336BZ_2V5")
      (footprint "TO92")
      (description "2.5V Voltage Reference")
      (fields (field (name "PUBLISHER") "Altium Limited"))
      (libsource (lib "ST Power Mgt Voltage Reference") (part "LM336BZ"))
    )
    (comp (ref "U3")
      (value "STM32H743VGT6")
      (footprint "QFP50P1600X1600X160-100N")
      (fields (field (name "MF") "STMicroelectronics"))
      (libsource (lib "STM32H743VGT6") (part "STM32H743VGT6"))
    )
    (comp (ref "U4")
      (value "PRTR5V")
      (footprint "SOT143L")
      (libsource (lib "Integrated_Library") (part "PRTR5V"))
    )
    (comp (ref "U5")
      (value "AD8021")
      (footprint "SO8_N")
      (description "General-Purpose Single J-FET Operational Amplifier")
      (fields (field (name "PUBLISHER") "Altium Limited"))
      (libsource (lib "ST Operational Amplifier") (part "MC33001D"))
    )
    (comp (ref "U6")
      (value "PRTR5V")
      (footprint "SOT143L")
      (libsource (lib "Integrated_Library") (part "PRTR5V"))
    )
    (comp (ref "U7")
      (value "PRTR5V")
      (footprint "SOT143L")
      (libsource (lib "Integrated_Library") (part "PRTR5V"))
    )
    (comp (ref "U8")
      (value "PRTR5V")
      (footprint "SOT143L")
      (libsource (lib "Integrated_Library") (part "PRTR5V"))
    )
    (comp (ref "U9")
      (value "AD8021")
      (footprint "SO8_N")
      (description "General-Purpose Single J-FET Operational Amplifier")
      (fields (field (name "PUBLISHER") "Altium Limited"))
      (libsource (lib "ST Operational Amplifier") (part "MC33001D"))
    )
  )
  (nets
    (net (code "1") (name "/ADC_Ch1") (class "Default")
      (node (ref "C31") (pin "2") (pinfunction "2_2") (pintype "passive"))
      (node (ref "R29") (pin "1") (pinfunction "1_1") (pintype "passive"))
      (node (ref "U3") (pin "30") (pinfunction "PA6-SPI1_MISO_30") (pintype "passive"))
    )
    (net (code "2") (name "/ADC_Ch2") (class "Default")
      (node (ref "C53") (pin "2") (pinfunction "2_2") (pintype "passive"))
      (node (ref "R43") (pin "1") (pinfunction "1_1") (pintype "passive"))
      (node (ref "U3") (pin "32") (pinfunction "PC4_32") (pintype "bidirectional"))
    )
    (net (code "3") (name "/ADC_Ch3_Direct") (class "Default")
      (node (ref "C73") (pin "2") (pinfunction "2_2") (pintype "passive"))
      (node (ref "R53") (pin "1") (pinfunction "1_1") (pintype "passive"))
      (node (ref "U3") (pin "17") (pinfunction "PC2_C-SPI2_MISO_17") (pintype "passive"))
    )
    (net (code "4") (name "/ADC_Ch3_Direct_In") (class "Default")
      (node (ref "R53") (pin "2") (pinfunction "2_2") (pintype "passive"))
    )
    (net (code "5") (name "/I2C_SCL") (class "Default")
      (node (ref "H_I1") (pin "1") (pinfunction "1_1") (pintype "passive"))
      (node (ref "R28") (pin "1") (pinfunction "1_1") (pintype "passive"))
      (node (ref "R31") (pin "1") (pinfunction "1_1") (pintype "passive"))
      (node (ref "U7") (pin "2") (pinfunction "2_2") (pintype "passive"))
    )
    (net (code "6") (name "/I2C_SDA") (class "Default")
      (node (ref "H_I1") (pin "2") (pinfunction "2_2") (pintype "passive"))
      (node (ref "R30") (pin "1") (pinfunction "1_1") (pintype "passive"))
      (node (ref "R32") (pin "1") (pinfunction "1_1") (pintype "passive"))
      (node (ref "U7") (pin "3") (pinfunction "3_3") (pintype "passive"))
    )
    (net (code "7") (name "/InNegative_1") (class "Default")
      (node (ref "C24") (pin "1") (pinfunction "1_1") (pintype "passive"))
      (node (ref "S_N1") (pin "2") (pinfunction "2_2") (pintype "passive"))
    )
    (net (code "8") (name "/InNegative_2") (class "Default")
      (node (ref "C39") (pin "1") (pinfunction "1_1") (pintype "passive"))
      (node (ref "S_N2") (pin "2") (pinfunction "2_2") (pintype "passive"))
    )
    (net (code "9") (name "/InPlus_1") (class "Default")
      (node (ref "C29") (pin "1") (pinfunction "1_1") (pintype "passive"))
      (node (ref "S_P1") (pin "2") (pinfunction "2_2") (pintype "passive"))
    )
    (net (code "10") (name "/InPlus_2") (class "Default")
      (node (ref "C49") (pin "1") (pinfunction "1_1") (pintype "passive"))
      (node (ref "S_P2") (pin "2") (pinfunction "2_2") (pintype "passive"))
    )
    (net (code "11") (name "/Input_1") (class "Default")
      (node (ref "J1") (pin "1") (pinfunction "Signal_1") (pintype "input"))
      (node (ref "S_N1") (pin "3") (pinfunction "3_3") (pintype "passive"))
      (node (ref "S_P1") (pin "3") (pinfunction "3_3") (pintype "passive"))
    )
    (net (code "12") (name "/Input_2") (class "Default")
      (node (ref "J2") (pin "1") (pinfunction "Signal_1") (pintype "input"))
      (node (ref "S_N2") (pin "3") (pinfunction "3_3") (pintype "passive"))
      (node (ref "S_P2") (pin "3") (pinfunction "3_3") (pintype "passive"))
    )
    (net (code "13") (name "/Op1_Neg") (class "Default")
      (node (ref "C25") (pin "1") (pinfunction "1_1") (pintype "passive"))
      (node (ref "R21") (pin "2") (pinfunction "2_2") (pintype "passive"))
      (node (ref "R22") (pin "1") (pinfunction "1_1") (pintype "passive"))
      (node (ref "S_G1") (pin "1") (pinfunction "1_1") (pintype "passive"))
      (node (ref "S_G1") (pin "3") (pinfunction "3_3") (pintype "passive"))
      (node (ref "S_G1") (pin "5") (pinfunction "5_5") (pintype "passive"))
      (node (ref "S_G1") (pin "7") (pinfunction "7_7") (pintype "passive"))
      (node (ref "U5") (pin "2") (pinfunction "IN-_2") (pintype "input"))
    )
    (net (code "14") (name "/Op1_Pos") (class "Default")
      (node (ref "C30") (pin "2") (pinfunction "2_2") (pintype "passive"))
      (node (ref "R34") (pin "2") (pinfunction "2_2") (pintype "passive"))
      (node (ref "U5") (pin "3") (pinfunction "IN+_3") (pintype "input"))
    )
    (net (code "15") (name "/Op1_out") (class "Default")
      (node (ref "C20") (pin "2") (pinfunction "2_2") (pintype "passive"))
      (node (ref "C21") (pin "2") (pinfunction "2_2") (pintype "passive"))
      (node (ref "C22") (pin "2") (pinfunction "2_2") (pintype "passive"))
      (node (ref "C23") (pin "2") (pinfunction "2_2") (pintype "passive"))
      (node (ref "C25") (pin "2") (pinfunction "2_2") (pintype "passive"))
      (node (ref "R12") (pin "2") (pinfunction "2_2") (pintype "passive"))
      (node (ref "R13") (pin "2") (pinfunction "2_2") (pintype "passive"))
      (node (ref "R14") (pin "2") (pinfunction "2_2") (pintype "passive"))
      (node (ref "R18") (pin "2") (pinfunction "2_2") (pintype "passive"))
      (node (ref "R22") (pin "2") (pinfunction "2_2") (pintype "passive"))
      (node (ref "R29") (pin "2") (pinfunction "2_2") (pintype "passive"))
      (node (ref "U5") (pin "6") (pinfunction "OUT_6") (pintype "output"))
    )
    (net (code "16") (name "/Op2_Neg") (class "Default")
      (node (ref "C40") (pin "1") (pinfunction "1_1") (pintype "passive"))
      (node (ref "R40") (pin "2") (pinfunction "2_2") (pintype "passive"))
      (node (ref "R41") (pin "1") (pinfunction "1_1") (pintype "passive"))
      (node (ref "S_G2") (pin "1") (pinfunction "1_1") (pintype "passive"))
      (node (ref "S_G2") (pin "3") (pinfunction "3_3") (pintype "passive"))
      (node (ref "S_G2") (pin "5") (pinfunction "5_5") (pintype "passive"))
      (node (ref "S_G2") (pin "7") (pinfunction "7_7") (pintype "passive"))
      (node (ref "U9") (pin "2") (pinfunction "IN-_2") (pintype "input"))
    )
    (net (code "17") (name "/Op2_Pos") (class "Default")
      (node (ref "C50") (pin "2") (pinfunction "2_2") (pintype "passive"))
      (node (ref "R45") (pin "2") (pinfunction "2_2") (pintype "passive"))
      (node (ref "U9") (pin "3") (pinfunction "IN+_3") (pintype "input"))
    )
    (net (code "18") (name "/Op2_out") (class "Default")
      (node (ref "C35") (pin "2") (pinfunction "2_2") (pintype "passive"))
      (node (ref "C36") (pin "2") (pinfunction "2_2") (pintype "passive"))
      (node (ref "C37") (pin "2") (pinfunction "2_2") (pintype "passive"))
      (node (ref "C38") (pin "2") (pinfunction "2_2") (pintype "passive"))
      (node (ref "C40") (pin "2") (pinfunction "2_2") (pintype "passive"))
      (node (ref "R36") (pin "2") (pinfunction "2_2") (pintype "passive"))
      (node (ref "R37") (pin "2") (pinfunction "2_2") (pintype "passive"))
      (node (ref "R38") (pin "2") (pinfunction "2_2") (pintype "passive"))
      (node (ref "R39") (pin "2") (pinfunction "2_2") (pintype "passive"))
      (node (ref "R41") (pin "2") (pinfunction "2_2") (pintype "passive"))
      (node (ref "R43") (pin "2") (pinfunction "2_2") (pintype "passive"))
      (node (ref "U9") (pin "6") (pinfunction "OUT_6") (pintype "output"))
    )
    (net (code "19") (name "/OpAmpEn1") (class "Default")
      (node (ref "C27") (pin "2") (pinfunction "2_2") (pintype "passive"))
      (node (ref "R15") (pin "1") (pinfunction "1_1") (pintype "passive"))
      (node (ref "R27") (pin "2") (pinfunction "2_2") (pintype "passive"))
      (node (ref "U5") (pin "8") (pinfunction "NC_8") (pintype "passive"))
    )
    (net (code "20") (name "/OpAmpEn2") (class "Default")
      (node (ref "C42") (pin "2") (pinfunction "2_2") (pintype "passive"))
      (node (ref "R16") (pin "1") (pinfunction "1_1") (pintype "passive"))
      (node (ref "R42") (pin "2") (pinfunction "2_2") (pintype "passive"))
      (node (ref "U9") (pin "8") (pinfunction "NC_8") (pintype "passive"))
    )
    (net (code "21") (name "/OpAmpEn3") (class "Default")
      (node (ref "R17") (pin "1") (pinfunction "1_1") (pintype "passive"))
    )
    (net (code "22") (name "/SWCLK") (class "Default")
      (node (ref "H_Program1") (pin "1") (pinfunction "1_1") (pintype "passive"))
      (node (ref "R26") (pin "1") (pinfunction "1_1") (pintype "passive"))
      (node (ref "U6") (pin "2") (pinfunction "2_2") (pintype "passive"))
    )
    (net (code "23") (name "/SWDIO") (class "Default")
      (node (ref "H_Program1") (pin "2") (pinfunction "2_2") (pintype "passive"))
      (node (ref "R25") (pin "1") (pinfunction "1_1") (pintype "passive"))
      (node (ref "U6") (pin "3") (pinfunction "3_3") (pintype "passive"))
    )
    (net (code "24") (name "/UART_DE") (class "Default")
      (node (ref "R35") (pin "1") (pinfunction "1_1") (pintype "passive"))
    )
    (net (code "25") (name "/UART_Rx") (class "Default")
      (node (ref "H_COM1") (pin "0") (pinfunction "0_0") (pintype "passive"))
      (node (ref "R20") (pin "1") (pinfunction "1_1") (pintype "passive"))
      (node (ref "R24") (pin "2") (pinfunction "2_2") (pintype "passive"))
      (node (ref "U8") (pin "2") (pinfunction "2_2") (pintype "passive"))
    )
    (net (code "26") (name "/UART_Tx") (class "Default")
      (node (ref "H_COM1") (pin "2") (pinfunction "2_2") (pintype "passive"))
      (node (ref "R19") (pin "1") (pinfunction "1_1") (pintype "passive"))
      (node (ref "R23") (pin "2") (pinfunction "2_2") (pintype "passive"))
      (node (ref "U8") (pin "3") (pinfunction "3_3") (pintype "passive"))
    )
    (net (code "27") (name "/UBS_DN") (class "Default")
      (node (ref "S_PC1") (pin "1") (pinfunction "1_1") (pintype "passive"))
      (node (ref "U3") (pin "70") (pinfunction "PA11-USB_OTG_FS_DM_70") (pintype "passive"))
      (node (ref "U4") (pin "3") (pinfunction "3_3") (pintype "passive"))
    )
    (net (code "28") (name "/UBS_DP") (class "Default")
      (node (ref "S_PC1") (pin "2") (pinfunction "2_2") (pintype "passive"))
      (node (ref "U3") (pin "71") (pinfunction "PA12-USB_OTG_FS_DP_71") (pintype "passive"))
      (node (ref "U4") (pin "2") (pinfunction "2_2") (pintype "passive"))
    )
    (net (code "29") (name "/VACC_IN") (class "Default")
      (node (ref "C57") (pin "1") (pinfunction "1_1") (pintype "passive"))
      (node (ref "LD2") (pin "3") (pinfunction "Vi_3") (pintype "passive"))
      (node (ref "R48") (pin "2") (pinfunction "2_2") (pintype "passive"))
    )
    (net (code "30") (name "/VADD_IN") (class "Default")
      (node (ref "C43") (pin "1") (pinfunction "1_1") (pintype "passive"))
      (node (ref "LD1") (pin "3") (pinfunction "Vi_3") (pintype "passive"))
      (node (ref "R46") (pin "2") (pinfunction "2_2") (pintype "passive"))
    )
    (net (code "31") (name "/VANALOG_IN") (class "Default")
      (node (ref "C47") (pin "2") (pinfunction "2_2") (pintype "passive"))
      (node (ref "DC_To_DC1") (pin "1") (pinfunction "Vin_1") (pintype "passive"))
      (node (ref "L2") (pin "1") (pinfunction "1_1") (pintype "passive"))
      (node (ref "R47") (pin "2") (pinfunction "2_2") (pintype "passive"))
    )
    (net (code "32") (name "/Vref_2V5") (class "Default")
      (node (ref "C13") (pin "2") (pinfunction "2_2") (pintype "passive"))
      (node (ref "C14") (pin "2") (pinfunction "2_2") (pintype "passive"))
      (node (ref "Pot_Vb1") (pin "0") (pinfunction "0_0") (pintype "passive"))
      (node (ref "R1") (pin "2") (pinfunction "2_2") (pintype "passive"))
      (node (ref "U1") (pin "1") (pinfunction "OUT_1") (pintype "output"))
      (node (ref "U3") (pin "20") (pinfunction "VREF+_20") (pintype "power_in"))
    )
    (net (code "33") (name "AVCC") (class "Default")
      (node (ref "C1") (pin "2") (pinfunction "2_2") (pintype "passive"))
      (node (ref "C26") (pin "2") (pinfunction "2_2") (pintype "passive"))
      (node (ref "C41") (pin "2") (pinfunction "2_2") (pintype "passive"))
      (node (ref "C61") (pin "2") (pinfunction "2_2") (pintype "passive"))
      (node (ref "C62") (pin "1") (pinfunction "1_1") (pintype "passive"))
      (node (ref "L2") (pin "2") (pinfunction "2_2") (pintype "passive"))
      (node (ref "R2") (pin "2") (pinfunction "2_2") (pintype "passive"))
      (node (ref "U1") (pin "4") (pinfunction "V+_4") (pintype "power_in"))
      (node (ref "U5") (pin "7") (pinfunction "V+_7") (pintype "power_in"))
      (node (ref "U9") (pin "7") (pinfunction "V+_7") (pintype "power_in"))
    )
    (net (code "34") (name "AVCC_3V3") (class "Default")
      (node (ref "C10") (pin "2") (pinfunction "2_2") (pintype "passive"))
      (node (ref "C59") (pin "1") (pinfunction "1_1") (pintype "passive"))
      (node (ref "C60") (pin "1") (pinfunction "1_1") (pintype "passive"))
      (node (ref "LD2") (pin "2") (pinfunction "Vo_2") (pintype "passive"))
      (node (ref "LD2") (pin "4") (pinfunction "Vo_4") (pintype "passive"))
      (node (ref "U3") (pin "21") (pinfunction "VDDA_21") (pintype "power_in"))
    )
    (net (code "35") (name "AVEE") (class "Default")
      (node (ref "C32") (pin "1") (pinfunction "1_1") (pintype "passive"))
      (node (ref "C34") (pin "1") (pinfunction "1_1") (pintype "passive"))
      (node (ref "C51") (pin "2") (pinfunction "2_2") (pintype "passive"))
      (node (ref "C52") (pin "2") (pinfunction "2_2") (pintype "passive"))
      (node (ref "C54") (pin "1") (pinfunction "1_1") (pintype "passive"))
      (node (ref "C56") (pin "1") (pinfunction "1_1") (pintype "passive"))
      (node (ref "L1") (pin "2") (pinfunction "2_2") (pintype "passive"))
      (node (ref "U5") (pin "4") (pinfunction "V-_4") (pintype "power_in"))
      (node (ref "U9") (pin "4") (pinfunction "V-_4") (pintype "power_in"))
    )
    (net (code "36") (name "DVCC_3V3") (class "Default")
      (node (ref "C45") (pin "1") (pinfunction "1_1") (pintype "passive"))
      (node (ref "C46") (pin "1") (pinfunction "1_1") (pintype "passive"))
      (node (ref "C5") (pin "2") (pinfunction "2_2") (pintype "passive"))
      (node (ref "C6") (pin "2") (pinfunction "2_2") (pintype "passive"))
      (node (ref "C7") (pin "2") (pinfunction "2_2") (pintype "passive"))
      (node (ref "C8") (pin "2") (pinfunction "2_2") (pintype "passive"))
      (node (ref "C9") (pin "2") (pinfunction "2_2") (pintype "passive"))
      (node (ref "H_I1") (pin "3") (pinfunction "3_3") (pintype "passive"))
      (node (ref "H_Program1") (pin "3") (pinfunction "3_3") (pintype "passive"))
      (node (ref "LD1") (pin "2") (pinfunction "Vo_2") (pintype "passive"))
      (node (ref "LD1") (pin "4") (pinfunction "Vo_4") (pintype "passive"))
      (node (ref "R11") (pin "2") (pinfunction "2_2") (pintype "passive"))
      (node (ref "R19") (pin "2") (pinfunction "2_2") (pintype "passive"))
      (node (ref "R20") (pin "2") (pinfunction "2_2") (pintype "passive"))
      (node (ref "R28") (pin "2") (pinfunction "2_2") (pintype "passive"))
      (node (ref "R30") (pin "2") (pinfunction "2_2") (pintype "passive"))
      (node (ref "U3") (pin "100") (pinfunction "VDD_100") (pintype "power_in"))
      (node (ref "U3") (pin "11") (pinfunction "VDD_2_11") (pintype "power_in"))
      (node (ref "U3") (pin "27") (pinfunction "VDD_3_27") (pintype "power_in"))
      (node (ref "U3") (pin "50") (pinfunction "VDD_4_50") (pintype "power_in"))
      (node (ref "U3") (pin "75") (pinfunction "VDD_5_75") (pintype "power_in"))
      (node (ref "U6") (pin "4") (pinfunction "4_4") (pintype "passive"))
      (node (ref "U7") (pin "4") (pinfunction "4_4") (pintype "passive"))
      (node (ref "U8") (pin "4") (pinfunction "4_4") (pintype "passive"))
    )
    (net (code "37") (name "GND") (class "Default")
      (node (ref "C1") (pin "1") (pinfunction "1_1") (pintype "passive"))
      (node (ref "C10") (pin "1") (pinfunction "1_1") (pintype "passive"))
      (node (ref "C11") (pin "1") (pinfunction "1_1") (pintype "passive"))
      (node (ref "C12") (pin "1") (pinfunction "1_1") (pintype "passive"))
      (node (ref "C13") (pin "1") (pinfunction "1_1") (pintype "passive"))
      (node (ref "C14") (pin "1") (pinfunction "1_1") (pintype "passive"))
      (node (ref "C15") (pin "1") (pinfunction "1_1") (pintype "passive"))
      (node (ref "C16") (pin "1") (pinfunction "1_1") (pintype "passive"))
      (node (ref "C17") (pin "1") (pinfunction "1_1") (pintype "passive"))
      (node (ref "C18") (pin "1") (pinfunction "1_1") (pintype "passive"))
      (node (ref "C19") (pin "1") (pinfunction "1_1") (pintype "passive"))
      (node (ref "C2") (pin "1") (pinfunction "1_1") (pintype "passive"))
      (node (ref "C26") (pin "1") (pinfunction "1_1") (pintype "passive"))
      (node (ref "C27") (pin "1") (pinfunction "1_1") (pintype "passive"))
      (node (ref "C28") (pin "2") (pinfunction "2_2") (pintype "passive"))
      (node (ref "C3") (pin "1") (pinfunction "1_1") (pintype "passive"))
      (node (ref "C31") (pin "1") (pinfunction "1_1") (pintype "passive"))
      (node (ref "C33") (pin "1") (pinfunction "1_1") (pintype "passive"))
      (node (ref "C34") (pin "2") (pinfunction "2_2") (pintype "passive"))
      (node (ref "C4") (pin "1") (pinfunction "1_1") (pintype "passive"))
      (node (ref "C41") (pin "1") (pinfunction "1_1") (pintype "passive"))
      (node (ref "C42") (pin "1") (pinfunction "1_1") (pintype "passive"))
      (node (ref "C43") (pin "2") (pinfunction "2_2") (pintype "passive"))
      (node (ref "C45") (pin "2") (pinfunction "2_2") (pintype "passive"))
      (node (ref "C46") (pin "2") (pinfunction "2_2") (pintype "passive"))
      (node (ref "C47") (pin "1") (pinfunction "1_1") (pintype "passive"))
      (node (ref "C48") (pin "1") (pinfunction "1_1") (pintype "passive"))
      (node (ref "C5") (pin "1") (pinfunction "1_1") (pintype "passive"))
      (node (ref "C51") (pin "1") (pinfunction "1_1") (pintype "passive"))
      (node (ref "C52") (pin "1") (pinfunction "1_1") (pintype "passive"))
      (node (ref "C53") (pin "1") (pinfunction "1_1") (pintype "passive"))
      (node (ref "C55") (pin "1") (pinfunction "1_1") (pintype "passive"))
      (node (ref "C56") (pin "2") (pinfunction "2_2") (pintype "passive"))
      (node (ref "C57") (pin "2") (pinfunction "2_2") (pintype "passive"))
      (node (ref "C59") (pin "2") (pinfunction "2_2") (pintype "passive"))
      (node (ref "C6") (pin "1") (pinfunction "1_1") (pintype "passive"))
      (node (ref "C60") (pin "2") (pinfunction "2_2") (pintype "passive"))
      (node (ref "C61") (pin "1") (pinfunction "1_1") (pintype "passive"))
      (node (ref "C62") (pin "2") (pinfunction "2_2") (pintype "passive"))
      (node (ref "C7") (pin "1") (pinfunction "1_1") (pintype "passive"))
      (node (ref "C73") (pin "1") (pinfunction "1_1") (pintype "passive"))
      (node (ref "C8") (pin "1") (pinfunction "1_1") (pintype "passive"))
      (node (ref "C9") (pin "1") (pinfunction "1_1") (pintype "passive"))
      (node (ref "DC_To_DC1") (pin "0") (pinfunction "GND_0") (pintype "passive"))
      (node (ref "DC_To_DC1") (pin "3") (pinfunction "Vo+_3") (pintype "passive"))
      (node (ref "H_COM1") (pin "1") (pinfunction "1_1") (pintype "passive"))
      (node (ref "H_I1") (pin "0") (pinfunction "0_0") (pintype "passive"))
      (node (ref "H_Program1") (pin "0") (pinfunction "0_0") (pintype "passive"))
      (node (ref "J1") (pin "2") (pinfunction "GND_2") (pintype "power_in"))
      (node (ref "J1") (pin "3") (pinfunction "GND_3") (pintype "power_in"))
      (node (ref "J1") (pin "4") (pinfunction "GND_4") (pintype "power_in"))
      (node (ref "J1") (pin "5") (pinfunction "GND_5") (pintype "power_in"))
      (node (ref "J2") (pin "2") (pinfunction "GND_2") (pintype "power_in"))
      (node (ref "J2") (pin "3") (pinfunction "GND_3") (pintype "power_in"))
      (node (ref "J2") (pin "4") (pinfunction "GND_4") (pintype "power_in"))
      (node (ref "J2") (pin "5") (pinfunction "GND_5") (pintype "power_in"))
      (node (ref "LD1") (pin "1") (pinfunction "GND_1") (pintype "passive"))
      (node (ref "LD2") (pin "1") (pinfunction "GND_1") (pintype "passive"))
      (node (ref "Pot_Vb1") (pin "2") (pinfunction "2_2") (pintype "passive"))
      (node (ref "R10") (pin "2") (pinfunction "2_2") (pintype "passive"))
      (node (ref "R27") (pin "1") (pinfunction "1_1") (pintype "passive"))
      (node (ref "R33") (pin "1") (pinfunction "1_1") (pintype "passive"))
      (node (ref "R42") (pin "1") (pinfunction "1_1") (pintype "passive"))
      (node (ref "R44") (pin "1") (pinfunction "1_1") (pintype "passive"))
      (node (ref "R7") (pin "1") (pinfunction "1_1") (pintype "passive"))
      (node (ref "R9") (pin "1") (pinfunction "1_1") (pintype "passive"))
      (node (ref "S1") (pin "1") (pinfunction "1_1") (pintype "passive"))
      (node (ref "S_N1") (pin "1") (pinfunction "1_1") (pintype "passive"))
      (node (ref "S_N2") (pin "1") (pinfunction "1_1") (pintype "passive"))
      (node (ref "S_P1") (pin "1") (pinfunction "1_1") (pintype "passive"))
      (node (ref "S_P2") (pin "1") (pinfunction "1_1") (pintype "passive"))
      (node (ref "S_PC1") (pin "3") (pinfunction "3_3") (pintype "passive"))
      (node (ref "S_PC1") (pin "4") (pinfunction "4_4") (pintype "passive"))
      (node (ref "S_PC1") (pin "5") (pinfunction "5_5") (pintype "passive"))
      (node (ref "U1") (pin "11") (pinfunction "V-_11") (pintype "power_in"))
      (node (ref "U2") (pin "1") (pinfunction "-V_1") (pintype "passive"))
      (node (ref "U3") (pin "10") (pinfunction "VSS_2_10") (pintype "power_in"))
      (node (ref "U3") (pin "19") (pinfunction "VSSA_19") (pintype "power_in"))
      (node (ref "U3") (pin "26") (pinfunction "VSS_3_26") (pintype "power_in"))
      (node (ref "U3") (pin "49") (pinfunction "VSS_4_49") (pintype "power_in"))
      (node (ref "U3") (pin "74") (pinfunction "VSS_5_74") (pintype "power_in"))
      (node (ref "U3") (pin "99") (pinfunction "VSS_99") (pintype "power_in"))
      (node (ref "U4") (pin "1") (pinfunction "1_1") (pintype "passive"))
      (node (ref "U5") (pin "1") (pinfunction "OS_NULL_1") (pintype "passive"))
      (node (ref "U6") (pin "1") (pinfunction "1_1") (pintype "passive"))
      (node (ref "U7") (pin "1") (pinfunction "1_1") (pintype "passive"))
      (node (ref "U8") (pin "1") (pinfunction "1_1") (pintype "passive"))
      (node (ref "U9") (pin "1") (pinfunction "OS_NULL_1") (pintype "passive"))
    )
    (net (code "38") (name "Net-(C20-Pad1)") (class "Default")
      (node (ref "C20") (pin "1") (pinfunction "1_1") (pintype "passive"))
      (node (ref "R12") (pin "1") (pinfunction "1_1") (pintype "passive"))
      (node (ref "S_G1") (pin "2") (pinfunction "2_2") (pintype "passive"))
    )
    (net (code "39") (name "Net-(C21-Pad1)") (class "Default")
      (node (ref "C21") (pin "1") (pinfunction "1_1") (pintype "passive"))
      (node (ref "R13") (pin "1") (pinfunction "1_1") (pintype "passive"))
      (node (ref "S_G1") (pin "4") (pinfunction "4_4") (pintype "passive"))
    )
    (net (code "40") (name "Net-(C22-Pad1)") (class "Default")
      (node (ref "C22") (pin "1") (pinfunction "1_1") (pintype "passive"))
      (node (ref "R14") (pin "1") (pinfunction "1_1") (pintype "passive"))
      (node (ref "S_G1") (pin "6") (pinfunction "6_6") (pintype "passive"))
    )
    (net (code "41") (name "Net-(C23-Pad1)") (class "Default")
      (node (ref "C23") (pin "1") (pinfunction "1_1") (pintype "passive"))
      (node (ref "R18") (pin "1") (pinfunction "1_1") (pintype "passive"))
      (node (ref "S_G1") (pin "8") (pinfunction "8_8") (pintype "passive"))
    )
    (net (code "42") (name "Net-(C24-Pad2)") (class "Default")
      (node (ref "C24") (pin "2") (pinfunction "2_2") (pintype "passive"))
      (node (ref "R21") (pin "1") (pinfunction "1_1") (pintype "passive"))
    )
    (net (code "43") (name "Net-(C29-Pad2)") (class "Default")
      (node (ref "C29") (pin "2") (pinfunction "2_2") (pintype "passive"))
      (node (ref "C30") (pin "1") (pinfunction "1_1") (pintype "passive"))
      (node (ref "R33") (pin "2") (pinfunction "2_2") (pintype "passive"))
    )
    (net (code "44") (name "Net-(C32-Pad2)") (class "Default")
      (node (ref "C32") (pin "2") (pinfunction "2_2") (pintype "passive"))
      (node (ref "U5") (pin "5") (pinfunction "OS_NULL_5") (pintype "passive"))
    )
    (net (code "45") (name "Net-(C35-Pad1)") (class "Default")
      (node (ref "C35") (pin "1") (pinfunction "1_1") (pintype "passive"))
      (node (ref "R36") (pin "1") (pinfunction "1_1") (pintype "passive"))
      (node (ref "S_G2") (pin "2") (pinfunction "2_2") (pintype "passive"))
    )
    (net (code "46") (name "Net-(C36-Pad1)") (class "Default")
      (node (ref "C36") (pin "1") (pinfunction "1_1") (pintype "passive"))
      (node (ref "R37") (pin "1") (pinfunction "1_1") (pintype "passive"))
      (node (ref "S_G2") (pin "4") (pinfunction "4_4") (pintype "passive"))
    )
    (net (code "47") (name "Net-(C37-Pad1)") (class "Default")
      (node (ref "C37") (pin "1") (pinfunction "1_1") (pintype "passive"))
      (node (ref "R38") (pin "1") (pinfunction "1_1") (pintype "passive"))
      (node (ref "S_G2") (pin "6") (pinfunction "6_6") (pintype "passive"))
    )
    (net (code "48") (name "Net-(C38-Pad1)") (class "Default")
      (node (ref "C38") (pin "1") (pinfunction "1_1") (pintype "passive"))
      (node (ref "R39") (pin "1") (pinfunction "1_1") (pintype "passive"))
      (node (ref "S_G2") (pin "8") (pinfunction "8_8") (pintype "passive"))
    )
    (net (code "49") (name "Net-(C39-Pad2)") (class "Default")
      (node (ref "C39") (pin "2") (pinfunction "2_2") (pintype "passive"))
      (node (ref "R40") (pin "1") (pinfunction "1_1") (pintype "passive"))
    )
    (net (code "50") (name "Net-(C49-Pad2)") (class "Default")
      (node (ref "C49") (pin "2") (pinfunction "2_2") (pintype "passive"))
      (node (ref "C50") (pin "1") (pinfunction "1_1") (pintype "passive"))
      (node (ref "R44") (pin "2") (pinfunction "2_2") (pintype "passive"))
    )
    (net (code "51") (name "Net-(C54-Pad2)") (class "Default")
      (node (ref "C54") (pin "2") (pinfunction "2_2") (pintype "passive"))
      (node (ref "U9") (pin "5") (pinfunction "OS_NULL_5") (pintype "passive"))
    )
    (net (code "52") (name "Net-(DC_To_DC1-Vo-)") (class "Default")
      (node (ref "C48") (pin "2") (pinfunction "2_2") (pintype "passive"))
      (node (ref "DC_To_DC1") (pin "2") (pinfunction "Vo-_2") (pintype "passive"))
      (node (ref "L1") (pin "1") (pinfunction "1_1") (pintype "passive"))
    )
    (net (code "53") (name "Net-(Pot_Vb1-Pad1)") (class "Default")
      (node (ref "Pot_Vb1") (pin "1") (pinfunction "1_1") (pintype "passive"))
      (node (ref "R5") (pin "1") (pinfunction "1_1") (pintype "passive"))
    )
    (net (code "54") (name "Net-(U1A-IN+)") (class "Default")
      (node (ref "C3") (pin "2") (pinfunction "2_2") (pintype "passive"))
      (node (ref "R3") (pin "2") (pinfunction "2_2") (pintype "passive"))
      (node (ref "U1") (pin "3") (pinfunction "IN+_3") (pintype "input"))
    )
    (net (code "55") (name "Net-(U1A-IN-)") (class "Default")
      (node (ref "R1") (pin "1") (pinfunction "1_1") (pintype "passive"))
      (node (ref "U1") (pin "2") (pinfunction "IN-_2") (pintype "input"))
    )
    (net (code "56") (name "Net-(U1B-IN+)") (class "Default")
      (node (ref "C4") (pin "2") (pinfunction "2_2") (pintype "passive"))
      (node (ref "R5") (pin "2") (pinfunction "2_2") (pintype "passive"))
      (node (ref "U1") (pin "5") (pinfunction "IN+_5") (pintype "input"))
    )
    (net (code "57") (name "Net-(U1B-IN-)") (class "Default")
      (node (ref "R4") (pin "1") (pinfunction "1_1") (pintype "passive"))
      (node (ref "U1") (pin "6") (pinfunction "IN-_6") (pintype "input"))
    )
    (net (code "58") (name "Net-(U1C-IN+)") (class "Default")
      (node (ref "R7") (pin "2") (pinfunction "2_2") (pintype "passive"))
      (node (ref "U1") (pin "10") (pinfunction "IN+_10") (pintype "input"))
    )
    (net (code "59") (name "Net-(U1C-IN-)") (class "Default")
      (node (ref "R6") (pin "1") (pinfunction "1_1") (pintype "passive"))
      (node (ref "U1") (pin "9") (pinfunction "IN-_9") (pintype "input"))
    )
    (net (code "60") (name "Net-(U1C-OUT)") (class "Default")
      (node (ref "R6") (pin "2") (pinfunction "2_2") (pintype "passive"))
      (node (ref "U1") (pin "8") (pinfunction "OUT_8") (pintype "output"))
    )
    (net (code "61") (name "Net-(U1D-IN+)") (class "Default")
      (node (ref "R9") (pin "2") (pinfunction "2_2") (pintype "passive"))
      (node (ref "U1") (pin "12") (pinfunction "IN+_12") (pintype "input"))
    )
    (net (code "62") (name "Net-(U1D-IN-)") (class "Default")
      (node (ref "R8") (pin "1") (pinfunction "1_1") (pintype "passive"))
      (node (ref "U1") (pin "13") (pinfunction "IN-_13") (pintype "input"))
    )
    (net (code "63") (name "Net-(U1D-OUT)") (class "Default")
      (node (ref "R8") (pin "2") (pinfunction "2_2") (pintype "passive"))
      (node (ref "U1") (pin "14") (pinfunction "OUT_14") (pintype "output"))
    )
    (net (code "64") (name "Net-(U2-+V)") (class "Default")
      (node (ref "C2") (pin "2") (pinfunction "2_2") (pintype "passive"))
      (node (ref "R2") (pin "1") (pinfunction "1_1") (pintype "passive"))
      (node (ref "R3") (pin "1") (pinfunction "1_1") (pintype "passive"))
      (node (ref "U2") (pin "2") (pinfunction "+V_2") (pintype "passive"))
    )
    (net (code "65") (name "Net-(U3A-PA0-UART4_TX)") (class "Default")
      (node (ref "R15") (pin "2") (pinfunction "2_2") (pintype "passive"))
      (node (ref "U3") (pin "22") (pinfunction "PA0-UART4_TX_22") (pintype "passive"))
    )
    (net (code "66") (name "Net-(U3A-PA1-UART4_RX)") (class "Default")
      (node (ref "R16") (pin "2") (pinfunction "2_2") (pintype "passive"))
      (node (ref "U3") (pin "23") (pinfunction "PA1-UART4_RX_23") (pintype "passive"))
    )
    (net (code "67") (name "Net-(U3A-PA2)") (class "Default")
      (node (ref "R17") (pin "2") (pinfunction "2_2") (pintype "passive"))
      (node (ref "U3") (pin "24") (pinfunction "PA2_24") (pintype "bidirectional"))
    )
    (net (code "68") (name "Net-(U3A-PA13-DEBUG_JTMS-SWDIO)") (class "Default")
      (node (ref "R25") (pin "2") (pinfunction "2_2") (pintype "passive"))
      (node (ref "U3") (pin "72") (pinfunction "PA13-DEBUG_JTMS-SWDIO_72") (pintype "passive"))
    )
    (net (code "69") (name "Net-(U3A-PA14-DEBUG_JTCK-SWCLK)") (class "Default")
      (node (ref "R26") (pin "2") (pinfunction "2_2") (pintype "passive"))
      (node (ref "U3") (pin "76") (pinfunction "PA14-DEBUG_JTCK-SWCLK_76") (pintype "passive"))
    )
    (net (code "70") (name "Net-(U3A-PB6-I2C1_SCL)") (class "Default")
      (node (ref "R31") (pin "2") (pinfunction "2_2") (pintype "passive"))
      (node (ref "U3") (pin "92") (pinfunction "PB6-I2C1_SCL_92") (pintype "passive"))
    )
    (net (code "71") (name "Net-(U3A-PB7-I2C1_SDA)") (class "Default")
      (node (ref "R32") (pin "2") (pinfunction "2_2") (pintype "passive"))
      (node (ref "U3") (pin "93") (pinfunction "PB7-I2C1_SDA_93") (pintype "passive"))
    )
    (net (code "72") (name "Net-(U3A-PB14-USART1_TX)") (class "Default")
      (node (ref "R35") (pin "2") (pinfunction "2_2") (pintype "passive"))
      (node (ref "U3") (pin "53") (pinfunction "PB14-USART1_TX_53") (pintype "passive"))
    )
    (net (code "73") (name "Net-(U3A-PC10)") (class "Default")
      (node (ref "R23") (pin "1") (pinfunction "1_1") (pintype "passive"))
      (node (ref "U3") (pin "78") (pinfunction "PC10_78") (pintype "bidirectional"))
    )
    (net (code "74") (name "Net-(U3A-PC11)") (class "Default")
      (node (ref "R24") (pin "1") (pinfunction "1_1") (pintype "passive"))
      (node (ref "U3") (pin "79") (pinfunction "PC11_79") (pintype "bidirectional"))
    )
    (net (code "75") (name "Net-(U3B-BOOT0)") (class "Default")
      (node (ref "R10") (pin "1") (pinfunction "1_1") (pintype "passive"))
      (node (ref "U3") (pin "94") (pinfunction "BOOT0_94") (pintype "input"))
    )
    (net (code "76") (name "Net-(U3B-NRST)") (class "Default")
      (node (ref "C19") (pin "2") (pinfunction "2_2") (pintype "passive"))
      (node (ref "R11") (pin "1") (pinfunction "1_1") (pintype "passive"))
      (node (ref "S1") (pin "2") (pinfunction "2_2") (pintype "passive"))
      (node (ref "U3") (pin "14") (pinfunction "NRST_14") (pintype "bidirectional"))
    )
    (net (code "77") (name "Net-(U3B-PH0-OSC_IN-RCC_OSC_IN)") (class "Default")
      (node (ref "*X1") (pin "1") (pinfunction "1_1") (pintype "passive"))
      (node (ref "C12") (pin "2") (pinfunction "2_2") (pintype "passive"))
      (node (ref "U3") (pin "12") (pinfunction "PH0-OSC_IN-RCC_OSC_IN_12") (pintype "passive"))
    )
    (net (code "78") (name "Net-(U3B-PH1-OSC_OUT)") (class "Default")
      (node (ref "*X1") (pin "0") (pinfunction "0_0") (pintype "passive"))
      (node (ref "C11") (pin "2") (pinfunction "2_2") (pintype "passive"))
      (node (ref "U3") (pin "13") (pinfunction "PH1-OSC_OUT_13") (pintype "bidirectional"))
    )
    (net (code "79") (name "Net-(U3C-VCAP1)") (class "Default")
      (node (ref "C15") (pin "2") (pinfunction "2_2") (pintype "passive"))
      (node (ref "C16") (pin "2") (pinfunction "2_2") (pintype "passive"))
      (node (ref "U3") (pin "48") (pinfunction "VCAP1_48") (pintype "power_in"))
    )
    (net (code "80") (name "Net-(U3C-VCAP2)") (class "Default")
      (node (ref "C17") (pin "2") (pinfunction "2_2") (pintype "passive"))
      (node (ref "C18") (pin "2") (pinfunction "2_2") (pintype "passive"))
      (node (ref "U3") (pin "73") (pinfunction "VCAP2_73") (pintype "power_in"))
    )
    (net (code "81") (name "USB_VCC") (class "Default")
      (node (ref "C28") (pin "1") (pinfunction "1_1") (pintype "passive"))
      (node (ref "R46") (pin "1") (pinfunction "1_1") (pintype "passive"))
      (node (ref "R47") (pin "1") (pinfunction "1_1") (pintype "passive"))
      (node (ref "R48") (pin "1") (pinfunction "1_1") (pintype "passive"))
      (node (ref "S_PC1") (pin "0") (pinfunction "0_0") (pintype "passive"))
      (node (ref "U4") (pin "4") (pinfunction "4_4") (pintype "passive"))
    )
    (net (code "82") (name "V_Bias") (class "Default")
      (node (ref "C33") (pin "2") (pinfunction "2_2") (pintype "passive"))
      (node (ref "C55") (pin "2") (pinfunction "2_2") (pintype "passive"))
      (node (ref "R34") (pin "1") (pinfunction "1_1") (pintype "passive"))
      (node (ref "R4") (pin "2") (pinfunction "2_2") (pintype "passive"))
      (node (ref "R45") (pin "1") (pinfunction "1_1") (pintype "passive"))
      (node (ref "U1") (pin "7") (pinfunction "OUT_7") (pintype "output"))
    )
    (net (code "83") (name "unconnected-(U2-ADJ-Pad3)") (class "Default")
      (node (ref "U2") (pin "3") (pinfunction "ADJ_3") (pintype "input"))
    )
    (net (code "84") (name "unconnected-(U3A-PA3-Pad25)") (class "Default")
      (node (ref "U3") (pin "25") (pinfunction "PA3_25") (pintype "bidirectional"))
    )
    (net (code "85") (name "unconnected-(U3A-PA4-SPI1_NSS-Pad28)") (class "Default")
      (node (ref "U3") (pin "28") (pinfunction "PA4-SPI1_NSS_28") (pintype "passive"))
    )
    (net (code "86") (name "unconnected-(U3A-PA5-SPI1_SCK-Pad29)") (class "Default")
      (node (ref "U3") (pin "29") (pinfunction "PA5-SPI1_SCK_29") (pintype "passive"))
    )
    (net (code "87") (name "unconnected-(U3A-PA7-SPI1_MOSI-Pad31)") (class "Default")
      (node (ref "U3") (pin "31") (pinfunction "PA7-SPI1_MOSI_31") (pintype "passive"))
    )
    (net (code "88") (name "unconnected-(U3A-PA8-Pad67)") (class "Default")
      (node (ref "U3") (pin "67") (pinfunction "PA8_67") (pintype "bidirectional"))
    )
    (net (code "89") (name "unconnected-(U3A-PA9-USB_OTG_FS_VBUS-Pad68)") (class "Default")
      (node (ref "U3") (pin "68") (pinfunction "PA9-USB_OTG_FS_VBUS_68") (pintype "passive"))
    )
    (net (code "90") (name "unconnected-(U3A-PA10-Pad69)") (class "Default")
      (node (ref "U3") (pin "69") (pinfunction "PA10_69") (pintype "bidirectional"))
    )
    (net (code "91") (name "unconnected-(U3A-PA15-Pad77)") (class "Default")
      (node (ref "U3") (pin "77") (pinfunction "PA15_77") (pintype "bidirectional"))
    )
    (net (code "92") (name "unconnected-(U3A-PB0-TIM3_CH3-Pad34)") (class "Default")
      (node (ref "U3") (pin "34") (pinfunction "PB0-TIM3_CH3_34") (pintype "passive"))
    )
    (net (code "93") (name "unconnected-(U3A-PB1-ADC1_INP5-Pad35)") (class "Default")
      (node (ref "U3") (pin "35") (pinfunction "PB1-ADC1_INP5_35") (pintype "passive"))
    )
    (net (code "94") (name "unconnected-(U3A-PB2-Pad36)") (class "Default")
      (node (ref "U3") (pin "36") (pinfunction "PB2_36") (pintype "bidirectional"))
    )
    (net (code "95") (name "unconnected-(U3A-PB3-DEBUG_JTDO-SWO-Pad89)") (class "Default")
      (node (ref "U3") (pin "89") (pinfunction "PB3-DEBUG_JTDO-SWO_89") (pintype "passive"))
    )
    (net (code "96") (name "unconnected-(U3A-PB4-Pad90)") (class "Default")
      (node (ref "U3") (pin "90") (pinfunction "PB4_90") (pintype "bidirectional"))
    )
    (net (code "97") (name "unconnected-(U3A-PB5-Pad91)") (class "Default")
      (node (ref "U3") (pin "91") (pinfunction "PB5_91") (pintype "bidirectional"))
    )
    (net (code "98") (name "unconnected-(U3A-PB8-Pad95)") (class "Default")
      (node (ref "U3") (pin "95") (pinfunction "PB8_95") (pintype "bidirectional"))
    )
    (net (code "99") (name "unconnected-(U3A-PB9-Pad96)") (class "Default")
      (node (ref "U3") (pin "96") (pinfunction "PB9_96") (pintype "bidirectional"))
    )
    (net (code "100") (name "unconnected-(U3A-PB10-Pad46)") (class "Default")
      (node (ref "U3") (pin "46") (pinfunction "PB10_46") (pintype "bidirectional"))
    )
    (net (code "101") (name "unconnected-(U3A-PB11-Pad47)") (class "Default")
      (node (ref "U3") (pin "47") (pinfunction "PB11_47") (pintype "bidirectional"))
    )
    (net (code "102") (name "unconnected-(U3A-PB12-SPI2_NSS-Pad51)") (class "Default")
      (node (ref "U3") (pin "51") (pinfunction "PB12-SPI2_NSS_51") (pintype "passive"))
    )
    (net (code "103") (name "unconnected-(U3A-PB13-SPI2_SCK-Pad52)") (class "Default")
      (node (ref "U3") (pin "52") (pinfunction "PB13-SPI2_SCK_52") (pintype "passive"))
    )
    (net (code "104") (name "unconnected-(U3A-PB15-USART1_RX-Pad54)") (class "Default")
      (node (ref "U3") (pin "54") (pinfunction "PB15-USART1_RX_54") (pintype "passive"))
    )
    (net (code "105") (name "unconnected-(U3A-PC0-Pad15)") (class "Default")
      (node (ref "U3") (pin "15") (pinfunction "PC0_15") (pintype "bidirectional"))
    )
    (net (code "106") (name "unconnected-(U3A-PC1-SPI2_MOSI-Pad16)") (class "Default")
      (node (ref "U3") (pin "16") (pinfunction "PC1-SPI2_MOSI_16") (pintype "passive"))
    )
    (net (code "107") (name "unconnected-(U3A-PC3_C-GPIO_Output-Pad18)") (class "Default")
      (node (ref "U3") (pin "18") (pinfunction "PC3_C-GPIO_Output_18") (pintype "passive"))
    )
    (net (code "108") (name "unconnected-(U3A-PC5-Pad33)") (class "Default")
      (node (ref "U3") (pin "33") (pinfunction "PC5_33") (pintype "bidirectional"))
    )
    (net (code "109") (name "unconnected-(U3A-PC6-Pad63)") (class "Default")
      (node (ref "U3") (pin "63") (pinfunction "PC6_63") (pintype "bidirectional"))
    )
    (net (code "110") (name "unconnected-(U3A-PC7-Pad64)") (class "Default")
      (node (ref "U3") (pin "64") (pinfunction "PC7_64") (pintype "bidirectional"))
    )
    (net (code "111") (name "unconnected-(U3A-PC8-Pad65)") (class "Default")
      (node (ref "U3") (pin "65") (pinfunction "PC8_65") (pintype "bidirectional"))
    )
    (net (code "112") (name "unconnected-(U3A-PC9-Pad66)") (class "Default")
      (node (ref "U3") (pin "66") (pinfunction "PC9_66") (pintype "bidirectional"))
    )
    (net (code "113") (name "unconnected-(U3A-PC12-Pad80)") (class "Default")
      (node (ref "U3") (pin "80") (pinfunction "PC12_80") (pintype "bidirectional"))
    )
    (net (code "114") (name "unconnected-(U3A-PC13-Pad7)") (class "Default")
      (node (ref "U3") (pin "7") (pinfunction "PC13_7") (pintype "bidirectional"))
    )
    (net (code "115") (name "unconnected-(U3A-PC14-OSC32_IN-Pad8)") (class "Default")
      (node (ref "U3") (pin "8") (pinfunction "PC14-OSC32_IN_8") (pintype "bidirectional"))
    )
    (net (code "116") (name "unconnected-(U3A-PC15-OSC32_OUT-Pad9)") (class "Default")
      (node (ref "U3") (pin "9") (pinfunction "PC15-OSC32_OUT_9") (pintype "bidirectional"))
    )
    (net (code "117") (name "unconnected-(U3A-PD0-Pad81)") (class "Default")
      (node (ref "U3") (pin "81") (pinfunction "PD0_81") (pintype "bidirectional"))
    )
    (net (code "118") (name "unconnected-(U3A-PD1-Pad82)") (class "Default")
      (node (ref "U3") (pin "82") (pinfunction "PD1_82") (pintype "bidirectional"))
    )
    (net (code "119") (name "unconnected-(U3A-PD2-Pad83)") (class "Default")
      (node (ref "U3") (pin "83") (pinfunction "PD2_83") (pintype "bidirectional"))
    )
    (net (code "120") (name "unconnected-(U3A-PD3-Pad84)") (class "Default")
      (node (ref "U3") (pin "84") (pinfunction "PD3_84") (pintype "bidirectional"))
    )
    (net (code "121") (name "unconnected-(U3A-PD4-Pad85)") (class "Default")
      (node (ref "U3") (pin "85") (pinfunction "PD4_85") (pintype "bidirectional"))
    )
    (net (code "122") (name "unconnected-(U3A-PD5-USART2_TX-Pad86)") (class "Default")
      (node (ref "U3") (pin "86") (pinfunction "PD5-USART2_TX_86") (pintype "passive"))
    )
    (net (code "123") (name "unconnected-(U3A-PD6-USART2_RX-Pad87)") (class "Default")
      (node (ref "U3") (pin "87") (pinfunction "PD6-USART2_RX_87") (pintype "passive"))
    )
    (net (code "124") (name "unconnected-(U3A-PD7-Pad88)") (class "Default")
      (node (ref "U3") (pin "88") (pinfunction "PD7_88") (pintype "bidirectional"))
    )
    (net (code "125") (name "unconnected-(U3A-PD8-USART3_TX-Pad55)") (class "Default")
      (node (ref "U3") (pin "55") (pinfunction "PD8-USART3_TX_55") (pintype "passive"))
    )
    (net (code "126") (name "unconnected-(U3A-PD9-USART3_RX-Pad56)") (class "Default")
      (node (ref "U3") (pin "56") (pinfunction "PD9-USART3_RX_56") (pintype "passive"))
    )
    (net (code "127") (name "unconnected-(U3A-PD10-Pad57)") (class "Default")
      (node (ref "U3") (pin "57") (pinfunction "PD10_57") (pintype "bidirectional"))
    )
    (net (code "128") (name "unconnected-(U3A-PD11-Pad58)") (class "Default")
      (node (ref "U3") (pin "58") (pinfunction "PD11_58") (pintype "bidirectional"))
    )
    (net (code "129") (name "unconnected-(U3A-PD12-TIM4_CH1-Pad59)") (class "Default")
      (node (ref "U3") (pin "59") (pinfunction "PD12-TIM4_CH1_59") (pintype "passive"))
    )
    (net (code "130") (name "unconnected-(U3A-PD13-TIM4_CH2-Pad60)") (class "Default")
      (node (ref "U3") (pin "60") (pinfunction "PD13-TIM4_CH2_60") (pintype "passive"))
    )
    (net (code "131") (name "unconnected-(U3A-PD14-TIM4_CH3-Pad61)") (class "Default")
      (node (ref "U3") (pin "61") (pinfunction "PD14-TIM4_CH3_61") (pintype "passive"))
    )
    (net (code "132") (name "unconnected-(U3A-PD15-TIM4_CH4-Pad62)") (class "Default")
      (node (ref "U3") (pin "62") (pinfunction "PD15-TIM4_CH4_62") (pintype "passive"))
    )
    (net (code "133") (name "unconnected-(U3B-PE0-Pad97)") (class "Default")
      (node (ref "U3") (pin "97") (pinfunction "PE0_97") (pintype "bidirectional"))
    )
    (net (code "134") (name "unconnected-(U3B-PE1-Pad98)") (class "Default")
      (node (ref "U3") (pin "98") (pinfunction "PE1_98") (pintype "bidirectional"))
    )
    (net (code "135") (name "unconnected-(U3B-PE2-Pad1)") (class "Default")
      (node (ref "U3") (pin "1") (pinfunction "PE2_1") (pintype "bidirectional"))
    )
    (net (code "136") (name "unconnected-(U3B-PE3-Pad2)") (class "Default")
      (node (ref "U3") (pin "2") (pinfunction "PE3_2") (pintype "bidirectional"))
    )
    (net (code "137") (name "unconnected-(U3B-PE4-Pad3)") (class "Default")
      (node (ref "U3") (pin "3") (pinfunction "PE4_3") (pintype "bidirectional"))
    )
    (net (code "138") (name "unconnected-(U3B-PE5-Pad4)") (class "Default")
      (node (ref "U3") (pin "4") (pinfunction "PE5_4") (pintype "bidirectional"))
    )
    (net (code "139") (name "unconnected-(U3B-PE6-Pad5)") (class "Default")
      (node (ref "U3") (pin "5") (pinfunction "PE6_5") (pintype "bidirectional"))
    )
    (net (code "140") (name "unconnected-(U3B-PE7-Pad37)") (class "Default")
      (node (ref "U3") (pin "37") (pinfunction "PE7_37") (pintype "bidirectional"))
    )
    (net (code "141") (name "unconnected-(U3B-PE8-Pad38)") (class "Default")
      (node (ref "U3") (pin "38") (pinfunction "PE8_38") (pintype "bidirectional"))
    )
    (net (code "142") (name "unconnected-(U3B-PE9-Pad39)") (class "Default")
      (node (ref "U3") (pin "39") (pinfunction "PE9_39") (pintype "bidirectional"))
    )
    (net (code "143") (name "unconnected-(U3B-PE10-Pad40)") (class "Default")
      (node (ref "U3") (pin "40") (pinfunction "PE10_40") (pintype "bidirectional"))
    )
    (net (code "144") (name "unconnected-(U3B-PE11-Pad41)") (class "Default")
      (node (ref "U3") (pin "41") (pinfunction "PE11_41") (pintype "bidirectional"))
    )
    (net (code "145") (name "unconnected-(U3B-PE12-Pad42)") (class "Default")
      (node (ref "U3") (pin "42") (pinfunction "PE12_42") (pintype "bidirectional"))
    )
    (net (code "146") (name "unconnected-(U3B-PE13-Pad43)") (class "Default")
      (node (ref "U3") (pin "43") (pinfunction "PE13_43") (pintype "bidirectional"))
    )
    (net (code "147") (name "unconnected-(U3B-PE14-Pad44)") (class "Default")
      (node (ref "U3") (pin "44") (pinfunction "PE14_44") (pintype "bidirectional"))
    )
    (net (code "148") (name "unconnected-(U3B-PE15-Pad45)") (class "Default")
      (node (ref "U3") (pin "45") (pinfunction "PE15_45") (pintype "bidirectional"))
    )
    (net (code "149") (name "unconnected-(U3C-VBAT-Pad6)") (class "Default")
      (node (ref "U3") (pin "6") (pinfunction "VBAT_6") (pintype "power_in"))
    )
  )
)
